# Mobo.net
KiCad netlist of a schematic drawn in Altium Designer
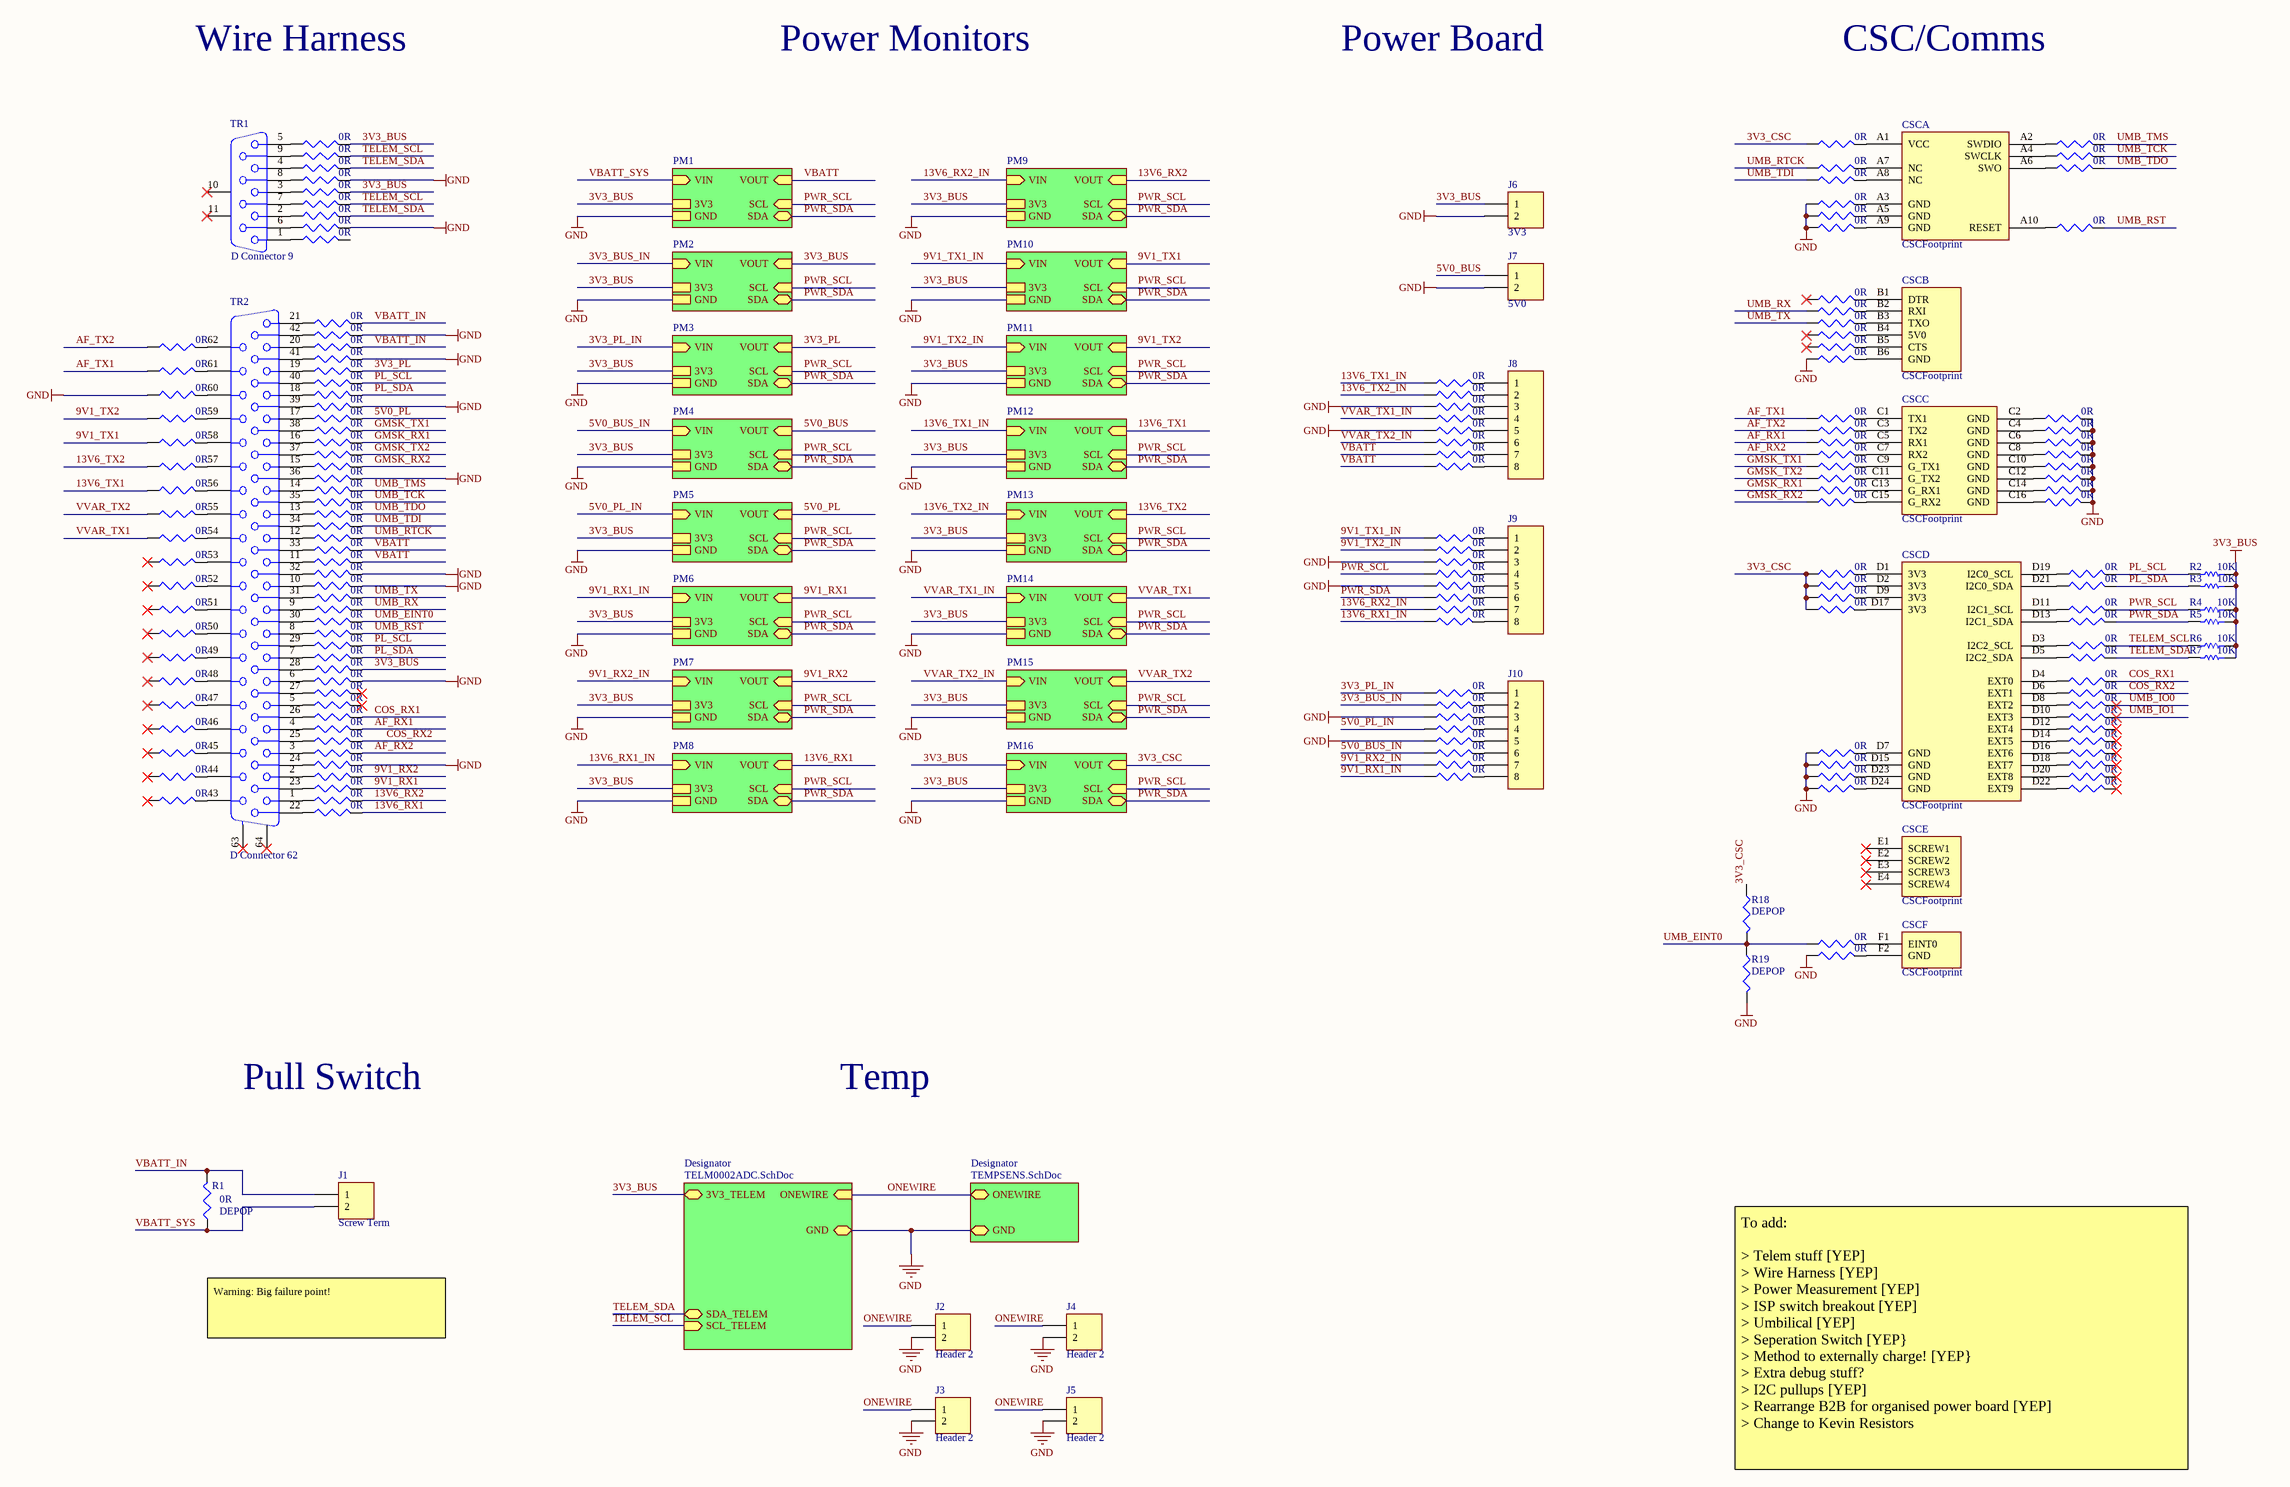
[diagram p0: Mobo.SchDoc]

(export (version "E")
  (design (tool "Eeschema 10.0.6"))
  (components
    (comp (ref "CSC")
      (value "CSCFootprint")
      (footprint "CSCFootprint")
      (libsource (lib "Tray2Mobo") (part "CSCFootprint"))
    )
    (comp (ref "J1")
      (value "Screw Term")
      (footprint "100mil ScrewTerm")
      (description "Header, 2-Pin")
      (fields (field (name "PUBLISHER") "Altium Limited"))
      (libsource (lib "Miscellaneous Connectors") (part "1WIRE"))
    )
    (comp (ref "J2")
      (value "Header 2")
      (footprint "HDR1X2")
      (description "Header, 2-Pin")
      (fields (field (name "PUBLISHER") "Altium Limited"))
      (libsource (lib "Miscellaneous Connectors") (part "1WIRE"))
    )
    (comp (ref "J3")
      (value "Header 2")
      (footprint "HDR1X2")
      (description "Header, 2-Pin")
      (fields (field (name "PUBLISHER") "Altium Limited"))
      (libsource (lib "Miscellaneous Connectors") (part "1WIRE"))
    )
    (comp (ref "J4")
      (value "Header 2")
      (footprint "HDR1X2")
      (description "Header, 2-Pin")
      (fields (field (name "PUBLISHER") "Altium Limited"))
      (libsource (lib "Miscellaneous Connectors") (part "1WIRE"))
    )
    (comp (ref "J5")
      (value "Header 2")
      (footprint "HDR1X2")
      (description "Header, 2-Pin")
      (fields (field (name "PUBLISHER") "Altium Limited"))
      (libsource (lib "Miscellaneous Connectors") (part "1WIRE"))
    )
    (comp (ref "J6")
      (value "3V3")
      (footprint "HDR1X2")
      (description "Header, 2-Pin")
      (fields (field (name "PUBLISHER") "Altium Limited"))
      (libsource (lib "Miscellaneous Connectors") (part "Header 2"))
    )
    (comp (ref "J7")
      (value "5V0")
      (footprint "HDR1X2")
      (description "Header, 2-Pin")
      (fields (field (name "PUBLISHER") "Altium Limited"))
      (libsource (lib "Miscellaneous Connectors") (part "Header 2"))
    )
    (comp (ref "J8")
      (value "J?")
      (footprint "MOLEX 444280802")
      (description "B2B RA Header")
      (libsource (lib "Tray2Mobo") (part "MOLEX 444280802"))
    )
    (comp (ref "J9")
      (value "J?")
      (footprint "MOLEX 444280802")
      (description "B2B RA Header")
      (libsource (lib "Tray2Mobo") (part "MOLEX 444280802"))
    )
    (comp (ref "J10")
      (value "J?")
      (footprint "MOLEX 444280802")
      (description "B2B RA Header")
      (libsource (lib "Tray2Mobo") (part "MOLEX 444280802"))
    )
    (comp (ref "R1")
      (value "DEPOP")
      (footprint "R0402M")
      (description "Resistor")
      (fields (field (name "ALTIUM_VALUE") "0R") (field (name "PUBLISHER") "Altium Limited"))
      (libsource (lib "Miscellaneous Devices") (part "Res3"))
    )
    (comp (ref "R2")
      (value "10K")
      (footprint "R0402M")
      (description "Resistor")
      (fields (field (name "PUBLISHER") "Altium Limited"))
      (libsource (lib "Miscellaneous Devices") (part "Res1"))
    )
    (comp (ref "R3")
      (value "10K")
      (footprint "R0402M")
      (description "Resistor")
      (fields (field (name "PUBLISHER") "Altium Limited"))
      (libsource (lib "Miscellaneous Devices") (part "Res1"))
    )
    (comp (ref "R4")
      (value "10K")
      (footprint "R0402M")
      (description "Resistor")
      (fields (field (name "PUBLISHER") "Altium Limited"))
      (libsource (lib "Miscellaneous Devices") (part "Res1"))
    )
    (comp (ref "R5")
      (value "10K")
      (footprint "R0402M")
      (description "Resistor")
      (fields (field (name "PUBLISHER") "Altium Limited"))
      (libsource (lib "Miscellaneous Devices") (part "Res1"))
    )
    (comp (ref "R6")
      (value "10K")
      (footprint "R0402M")
      (description "Resistor")
      (fields (field (name "PUBLISHER") "Altium Limited"))
      (libsource (lib "Miscellaneous Devices") (part "Res1"))
    )
    (comp (ref "R7")
      (value "10K")
      (footprint "R0402M")
      (description "Resistor")
      (fields (field (name "PUBLISHER") "Altium Limited"))
      (libsource (lib "Miscellaneous Devices") (part "Res1"))
    )
    (comp (ref "R18")
      (value "DEPOP")
      (footprint "R0402M")
      (description "Resistor")
      (fields (field (name "PUBLISHER") "Altium Limited"))
      (libsource (lib "Miscellaneous Devices") (part "Res3"))
    )
    (comp (ref "R19")
      (value "DEPOP")
      (footprint "R0402M")
      (description "Resistor")
      (fields (field (name "PUBLISHER") "Altium Limited"))
      (libsource (lib "Miscellaneous Devices") (part "Res3"))
    )
    (comp (ref "TR1")
      (value "D Connector 9")
      (footprint "HD-20 9 POS")
      (description "Receptacle Assembly, 9 Position, Right Angle")
      (fields (field (name "PUBLISHER") "Altium Limited"))
      (libsource (lib "Miscellaneous Connectors") (part "D Connector 9"))
    )
    (comp (ref "TR2")
      (value "D Connector 62")
      (footprint "HD-22 62 POS")
      (libsource (lib "Tray2Mobo") (part "Connector 62"))
    )
    (comp (ref "Z1")
      (value "0R")
      (footprint "Short")
      (description "Resistor")
      (fields (field (name "PUBLISHER") "Altium Limited"))
      (libsource (lib "Miscellaneous Devices") (part "Res3"))
    )
    (comp (ref "Z2")
      (value "0R")
      (footprint "Short")
      (description "Resistor")
      (fields (field (name "PUBLISHER") "Altium Limited"))
      (libsource (lib "Miscellaneous Devices") (part "Res3"))
    )
    (comp (ref "Z3")
      (value "0R")
      (footprint "Short")
      (description "Resistor")
      (fields (field (name "PUBLISHER") "Altium Limited"))
      (libsource (lib "Miscellaneous Devices") (part "Res3"))
    )
    (comp (ref "Z4")
      (value "0R")
      (footprint "Short")
      (description "Resistor")
      (fields (field (name "PUBLISHER") "Altium Limited"))
      (libsource (lib "Miscellaneous Devices") (part "Res3"))
    )
    (comp (ref "Z5")
      (value "0R")
      (footprint "Short")
      (description "Resistor")
      (fields (field (name "PUBLISHER") "Altium Limited"))
      (libsource (lib "Miscellaneous Devices") (part "Res3"))
    )
    (comp (ref "Z6")
      (value "0R")
      (footprint "Short")
      (description "Resistor")
      (fields (field (name "PUBLISHER") "Altium Limited"))
      (libsource (lib "Miscellaneous Devices") (part "Res3"))
    )
    (comp (ref "Z7")
      (value "0R")
      (footprint "Short")
      (description "Resistor")
      (fields (field (name "PUBLISHER") "Altium Limited"))
      (libsource (lib "Miscellaneous Devices") (part "Res3"))
    )
    (comp (ref "Z8")
      (value "0R")
      (footprint "Short")
      (description "Resistor")
      (fields (field (name "PUBLISHER") "Altium Limited"))
      (libsource (lib "Miscellaneous Devices") (part "Res3"))
    )
    (comp (ref "Z9")
      (value "0R")
      (footprint "Short")
      (description "Resistor")
      (fields (field (name "PUBLISHER") "Altium Limited"))
      (libsource (lib "Miscellaneous Devices") (part "Res3"))
    )
    (comp (ref "Z10")
      (value "0R")
      (footprint "Short")
      (description "Resistor")
      (fields (field (name "PUBLISHER") "Altium Limited"))
      (libsource (lib "Miscellaneous Devices") (part "Res3"))
    )
    (comp (ref "Z11")
      (value "0R")
      (footprint "Short")
      (description "Resistor")
      (fields (field (name "PUBLISHER") "Altium Limited"))
      (libsource (lib "Miscellaneous Devices") (part "Res3"))
    )
    (comp (ref "Z12")
      (value "0R")
      (footprint "Short")
      (description "Resistor")
      (fields (field (name "PUBLISHER") "Altium Limited"))
      (libsource (lib "Miscellaneous Devices") (part "Res3"))
    )
    (comp (ref "Z13")
      (value "0R")
      (footprint "Short")
      (description "Resistor")
      (fields (field (name "PUBLISHER") "Altium Limited"))
      (libsource (lib "Miscellaneous Devices") (part "Res3"))
    )
    (comp (ref "Z14")
      (value "0R")
      (footprint "Short")
      (description "Resistor")
      (fields (field (name "PUBLISHER") "Altium Limited"))
      (libsource (lib "Miscellaneous Devices") (part "Res3"))
    )
    (comp (ref "Z15")
      (value "0R")
      (footprint "Short")
      (description "Resistor")
      (fields (field (name "PUBLISHER") "Altium Limited"))
      (libsource (lib "Miscellaneous Devices") (part "Res3"))
    )
    (comp (ref "Z16")
      (value "0R")
      (footprint "Short")
      (description "Resistor")
      (fields (field (name "PUBLISHER") "Altium Limited"))
      (libsource (lib "Miscellaneous Devices") (part "Res3"))
    )
    (comp (ref "Z17")
      (value "0R")
      (footprint "Short")
      (description "Resistor")
      (fields (field (name "PUBLISHER") "Altium Limited"))
      (libsource (lib "Miscellaneous Devices") (part "Res3"))
    )
    (comp (ref "Z18")
      (value "0R")
      (footprint "Short")
      (description "Resistor")
      (fields (field (name "PUBLISHER") "Altium Limited"))
      (libsource (lib "Miscellaneous Devices") (part "Res3"))
    )
    (comp (ref "Z19")
      (value "0R")
      (footprint "Short")
      (description "Resistor")
      (fields (field (name "PUBLISHER") "Altium Limited"))
      (libsource (lib "Miscellaneous Devices") (part "Res3"))
    )
    (comp (ref "Z20")
      (value "0R")
      (footprint "Short")
      (description "Resistor")
      (fields (field (name "PUBLISHER") "Altium Limited"))
      (libsource (lib "Miscellaneous Devices") (part "Res3"))
    )
    (comp (ref "Z21")
      (value "0R")
      (footprint "Short")
      (description "Resistor")
      (fields (field (name "PUBLISHER") "Altium Limited"))
      (libsource (lib "Miscellaneous Devices") (part "Res3"))
    )
    (comp (ref "Z22")
      (value "0R")
      (footprint "Short")
      (description "Resistor")
      (fields (field (name "PUBLISHER") "Altium Limited"))
      (libsource (lib "Miscellaneous Devices") (part "Res3"))
    )
    (comp (ref "Z23")
      (value "0R")
      (footprint "Short")
      (description "Resistor")
      (fields (field (name "PUBLISHER") "Altium Limited"))
      (libsource (lib "Miscellaneous Devices") (part "Res3"))
    )
    (comp (ref "Z24")
      (value "0R")
      (footprint "Short")
      (description "Resistor")
      (fields (field (name "PUBLISHER") "Altium Limited"))
      (libsource (lib "Miscellaneous Devices") (part "Res3"))
    )
    (comp (ref "Z25")
      (value "0R")
      (footprint "Short")
      (description "Resistor")
      (fields (field (name "PUBLISHER") "Altium Limited"))
      (libsource (lib "Miscellaneous Devices") (part "Res3"))
    )
    (comp (ref "Z26")
      (value "0R")
      (footprint "Short")
      (description "Resistor")
      (fields (field (name "PUBLISHER") "Altium Limited"))
      (libsource (lib "Miscellaneous Devices") (part "Res3"))
    )
    (comp (ref "Z27")
      (value "0R")
      (footprint "Short")
      (description "Resistor")
      (fields (field (name "PUBLISHER") "Altium Limited"))
      (libsource (lib "Miscellaneous Devices") (part "Res3"))
    )
    (comp (ref "Z28")
      (value "0R")
      (footprint "Short")
      (description "Resistor")
      (fields (field (name "PUBLISHER") "Altium Limited"))
      (libsource (lib "Miscellaneous Devices") (part "Res3"))
    )
    (comp (ref "Z29")
      (value "0R")
      (footprint "Short")
      (description "Resistor")
      (fields (field (name "PUBLISHER") "Altium Limited"))
      (libsource (lib "Miscellaneous Devices") (part "Res3"))
    )
    (comp (ref "Z30")
      (value "0R")
      (footprint "Short")
      (description "Resistor")
      (fields (field (name "PUBLISHER") "Altium Limited"))
      (libsource (lib "Miscellaneous Devices") (part "Res3"))
    )
    (comp (ref "Z31")
      (value "0R")
      (footprint "Short")
      (description "Resistor")
      (fields (field (name "PUBLISHER") "Altium Limited"))
      (libsource (lib "Miscellaneous Devices") (part "Res3"))
    )
    (comp (ref "Z32")
      (value "0R")
      (footprint "Short")
      (description "Resistor")
      (fields (field (name "PUBLISHER") "Altium Limited"))
      (libsource (lib "Miscellaneous Devices") (part "Res3"))
    )
    (comp (ref "Z33")
      (value "0R")
      (footprint "Short")
      (description "Resistor")
      (fields (field (name "PUBLISHER") "Altium Limited"))
      (libsource (lib "Miscellaneous Devices") (part "Res3"))
    )
    (comp (ref "Z34")
      (value "0R")
      (footprint "Short")
      (description "Resistor")
      (fields (field (name "PUBLISHER") "Altium Limited"))
      (libsource (lib "Miscellaneous Devices") (part "Res3"))
    )
    (comp (ref "Z35")
      (value "0R")
      (footprint "Short")
      (description "Resistor")
      (fields (field (name "PUBLISHER") "Altium Limited"))
      (libsource (lib "Miscellaneous Devices") (part "Res3"))
    )
    (comp (ref "Z36")
      (value "0R")
      (footprint "Short")
      (description "Resistor")
      (fields (field (name "PUBLISHER") "Altium Limited"))
      (libsource (lib "Miscellaneous Devices") (part "Res3"))
    )
    (comp (ref "Z37")
      (value "0R")
      (footprint "Short")
      (description "Resistor")
      (fields (field (name "PUBLISHER") "Altium Limited"))
      (libsource (lib "Miscellaneous Devices") (part "Res3"))
    )
    (comp (ref "Z38")
      (value "0R")
      (footprint "Short")
      (description "Resistor")
      (fields (field (name "PUBLISHER") "Altium Limited"))
      (libsource (lib "Miscellaneous Devices") (part "Res3"))
    )
    (comp (ref "Z39")
      (value "0R")
      (footprint "Short")
      (description "Resistor")
      (fields (field (name "PUBLISHER") "Altium Limited"))
      (libsource (lib "Miscellaneous Devices") (part "Res3"))
    )
    (comp (ref "Z40")
      (value "0R")
      (footprint "Short")
      (description "Resistor")
      (fields (field (name "PUBLISHER") "Altium Limited"))
      (libsource (lib "Miscellaneous Devices") (part "Res3"))
    )
    (comp (ref "Z41")
      (value "0R")
      (footprint "Short")
      (description "Resistor")
      (fields (field (name "PUBLISHER") "Altium Limited"))
      (libsource (lib "Miscellaneous Devices") (part "Res3"))
    )
    (comp (ref "Z42")
      (value "0R")
      (footprint "Short")
      (description "Resistor")
      (fields (field (name "PUBLISHER") "Altium Limited"))
      (libsource (lib "Miscellaneous Devices") (part "Res3"))
    )
    (comp (ref "Z43")
      (value "0R")
      (footprint "Short")
      (description "Resistor")
      (fields (field (name "PUBLISHER") "Altium Limited"))
      (libsource (lib "Miscellaneous Devices") (part "Res3"))
    )
    (comp (ref "Z44")
      (value "0R")
      (footprint "Short")
      (description "Resistor")
      (fields (field (name "PUBLISHER") "Altium Limited"))
      (libsource (lib "Miscellaneous Devices") (part "Res3"))
    )
    (comp (ref "Z45")
      (value "0R")
      (footprint "Short")
      (description "Resistor")
      (fields (field (name "PUBLISHER") "Altium Limited"))
      (libsource (lib "Miscellaneous Devices") (part "Res3"))
    )
    (comp (ref "Z46")
      (value "0R")
      (footprint "Short")
      (description "Resistor")
      (fields (field (name "PUBLISHER") "Altium Limited"))
      (libsource (lib "Miscellaneous Devices") (part "Res3"))
    )
    (comp (ref "Z47")
      (value "0R")
      (footprint "Short")
      (description "Resistor")
      (fields (field (name "PUBLISHER") "Altium Limited"))
      (libsource (lib "Miscellaneous Devices") (part "Res3"))
    )
    (comp (ref "Z48")
      (value "0R")
      (footprint "Short")
      (description "Resistor")
      (fields (field (name "PUBLISHER") "Altium Limited"))
      (libsource (lib "Miscellaneous Devices") (part "Res3"))
    )
    (comp (ref "Z49")
      (value "0R")
      (footprint "Short")
      (description "Resistor")
      (fields (field (name "PUBLISHER") "Altium Limited"))
      (libsource (lib "Miscellaneous Devices") (part "Res3"))
    )
    (comp (ref "Z50")
      (value "0R")
      (footprint "Short")
      (description "Resistor")
      (fields (field (name "PUBLISHER") "Altium Limited"))
      (libsource (lib "Miscellaneous Devices") (part "Res3"))
    )
    (comp (ref "Z51")
      (value "0R")
      (footprint "Short")
      (description "Resistor")
      (fields (field (name "PUBLISHER") "Altium Limited"))
      (libsource (lib "Miscellaneous Devices") (part "Res3"))
    )
    (comp (ref "Z52")
      (value "0R")
      (footprint "Short")
      (description "Resistor")
      (fields (field (name "PUBLISHER") "Altium Limited"))
      (libsource (lib "Miscellaneous Devices") (part "Res3"))
    )
    (comp (ref "Z53")
      (value "0R")
      (footprint "Short")
      (description "Resistor")
      (fields (field (name "PUBLISHER") "Altium Limited"))
      (libsource (lib "Miscellaneous Devices") (part "Res3"))
    )
    (comp (ref "Z54")
      (value "0R")
      (footprint "Short")
      (description "Resistor")
      (fields (field (name "PUBLISHER") "Altium Limited"))
      (libsource (lib "Miscellaneous Devices") (part "Res3"))
    )
    (comp (ref "Z55")
      (value "0R")
      (footprint "Short")
      (description "Resistor")
      (fields (field (name "PUBLISHER") "Altium Limited"))
      (libsource (lib "Miscellaneous Devices") (part "Res3"))
    )
    (comp (ref "Z56")
      (value "0R")
      (footprint "Short")
      (description "Resistor")
      (fields (field (name "PUBLISHER") "Altium Limited"))
      (libsource (lib "Miscellaneous Devices") (part "Res3"))
    )
    (comp (ref "Z57")
      (value "0R")
      (footprint "Short")
      (description "Resistor")
      (fields (field (name "PUBLISHER") "Altium Limited"))
      (libsource (lib "Miscellaneous Devices") (part "Res3"))
    )
    (comp (ref "Z58")
      (value "0R")
      (footprint "Short")
      (description "Resistor")
      (fields (field (name "PUBLISHER") "Altium Limited"))
      (libsource (lib "Miscellaneous Devices") (part "Res3"))
    )
    (comp (ref "Z59")
      (value "0R")
      (footprint "Short")
      (description "Resistor")
      (fields (field (name "PUBLISHER") "Altium Limited"))
      (libsource (lib "Miscellaneous Devices") (part "Res3"))
    )
    (comp (ref "Z60")
      (value "0R")
      (footprint "Short")
      (description "Resistor")
      (fields (field (name "PUBLISHER") "Altium Limited"))
      (libsource (lib "Miscellaneous Devices") (part "Res3"))
    )
    (comp (ref "Z61")
      (value "0R")
      (footprint "Short")
      (description "Resistor")
      (fields (field (name "PUBLISHER") "Altium Limited"))
      (libsource (lib "Miscellaneous Devices") (part "Res3"))
    )
    (comp (ref "Z62")
      (value "0R")
      (footprint "Short")
      (description "Resistor")
      (fields (field (name "PUBLISHER") "Altium Limited"))
      (libsource (lib "Miscellaneous Devices") (part "Res3"))
    )
    (comp (ref "Z63")
      (value "0R")
      (footprint "Short")
      (description "Resistor")
      (fields (field (name "PUBLISHER") "Altium Limited"))
      (libsource (lib "Miscellaneous Devices") (part "Res3"))
    )
    (comp (ref "Z64")
      (value "0R")
      (footprint "Short")
      (description "Resistor")
      (fields (field (name "PUBLISHER") "Altium Limited"))
      (libsource (lib "Miscellaneous Devices") (part "Res3"))
    )
    (comp (ref "Z65")
      (value "0R")
      (footprint "Short")
      (description "Resistor")
      (fields (field (name "PUBLISHER") "Altium Limited"))
      (libsource (lib "Miscellaneous Devices") (part "Res3"))
    )
    (comp (ref "Z66")
      (value "0R")
      (footprint "Short")
      (description "Resistor")
      (fields (field (name "PUBLISHER") "Altium Limited"))
      (libsource (lib "Miscellaneous Devices") (part "Res3"))
    )
    (comp (ref "Z67")
      (value "0R")
      (footprint "Short")
      (description "Resistor")
      (fields (field (name "PUBLISHER") "Altium Limited"))
      (libsource (lib "Miscellaneous Devices") (part "Res3"))
    )
    (comp (ref "Z68")
      (value "0R")
      (footprint "Short")
      (description "Resistor")
      (fields (field (name "PUBLISHER") "Altium Limited"))
      (libsource (lib "Miscellaneous Devices") (part "Res3"))
    )
    (comp (ref "Z69")
      (value "0R")
      (footprint "Short")
      (description "Resistor")
      (fields (field (name "PUBLISHER") "Altium Limited"))
      (libsource (lib "Miscellaneous Devices") (part "Res3"))
    )
    (comp (ref "Z70")
      (value "0R")
      (footprint "Short")
      (description "Resistor")
      (fields (field (name "PUBLISHER") "Altium Limited"))
      (libsource (lib "Miscellaneous Devices") (part "Res3"))
    )
    (comp (ref "Z71")
      (value "0R")
      (footprint "Short")
      (description "Resistor")
      (fields (field (name "PUBLISHER") "Altium Limited"))
      (libsource (lib "Miscellaneous Devices") (part "Res3"))
    )
    (comp (ref "Z72")
      (value "0R")
      (footprint "Short")
      (description "Resistor")
      (fields (field (name "PUBLISHER") "Altium Limited"))
      (libsource (lib "Miscellaneous Devices") (part "Res3"))
    )
    (comp (ref "Z73")
      (value "0R")
      (footprint "Short")
      (description "Resistor")
      (fields (field (name "PUBLISHER") "Altium Limited"))
      (libsource (lib "Miscellaneous Devices") (part "Res3"))
    )
    (comp (ref "Z74")
      (value "0R")
      (footprint "Short")
      (description "Resistor")
      (fields (field (name "PUBLISHER") "Altium Limited"))
      (libsource (lib "Miscellaneous Devices") (part "Res3"))
    )
    (comp (ref "Z75")
      (value "0R")
      (footprint "Short")
      (description "Resistor")
      (fields (field (name "PUBLISHER") "Altium Limited"))
      (libsource (lib "Miscellaneous Devices") (part "Res3"))
    )
    (comp (ref "Z76")
      (value "0R")
      (footprint "Short")
      (description "Resistor")
      (fields (field (name "PUBLISHER") "Altium Limited"))
      (libsource (lib "Miscellaneous Devices") (part "Res3"))
    )
    (comp (ref "Z77")
      (value "0R")
      (footprint "Short")
      (description "Resistor")
      (fields (field (name "PUBLISHER") "Altium Limited"))
      (libsource (lib "Miscellaneous Devices") (part "Res3"))
    )
    (comp (ref "Z78")
      (value "0R")
      (footprint "Short")
      (description "Resistor")
      (fields (field (name "PUBLISHER") "Altium Limited"))
      (libsource (lib "Miscellaneous Devices") (part "Res3"))
    )
    (comp (ref "Z79")
      (value "0R")
      (footprint "Short")
      (description "Resistor")
      (fields (field (name "PUBLISHER") "Altium Limited"))
      (libsource (lib "Miscellaneous Devices") (part "Res3"))
    )
    (comp (ref "Z80")
      (value "0R")
      (footprint "Short")
      (description "Resistor")
      (fields (field (name "PUBLISHER") "Altium Limited"))
      (libsource (lib "Miscellaneous Devices") (part "Res3"))
    )
    (comp (ref "Z81")
      (value "0R")
      (footprint "Short")
      (description "Resistor")
      (fields (field (name "PUBLISHER") "Altium Limited"))
      (libsource (lib "Miscellaneous Devices") (part "Res3"))
    )
    (comp (ref "Z82")
      (value "0R")
      (footprint "Short")
      (description "Resistor")
      (fields (field (name "PUBLISHER") "Altium Limited"))
      (libsource (lib "Miscellaneous Devices") (part "Res3"))
    )
    (comp (ref "Z83")
      (value "0R")
      (footprint "Short")
      (description "Resistor")
      (fields (field (name "PUBLISHER") "Altium Limited"))
      (libsource (lib "Miscellaneous Devices") (part "Res3"))
    )
    (comp (ref "Z84")
      (value "0R")
      (footprint "Short")
      (description "Resistor")
      (fields (field (name "PUBLISHER") "Altium Limited"))
      (libsource (lib "Miscellaneous Devices") (part "Res3"))
    )
    (comp (ref "Z85")
      (value "0R")
      (footprint "Short")
      (description "Resistor")
      (fields (field (name "PUBLISHER") "Altium Limited"))
      (libsource (lib "Miscellaneous Devices") (part "Res3"))
    )
    (comp (ref "Z86")
      (value "0R")
      (footprint "Short")
      (description "Resistor")
      (fields (field (name "PUBLISHER") "Altium Limited"))
      (libsource (lib "Miscellaneous Devices") (part "Res3"))
    )
    (comp (ref "Z87")
      (value "0R")
      (footprint "Short")
      (description "Resistor")
      (fields (field (name "PUBLISHER") "Altium Limited"))
      (libsource (lib "Miscellaneous Devices") (part "Res3"))
    )
    (comp (ref "Z88")
      (value "0R")
      (footprint "Short")
      (description "Resistor")
      (fields (field (name "PUBLISHER") "Altium Limited"))
      (libsource (lib "Miscellaneous Devices") (part "Res3"))
    )
    (comp (ref "Z89")
      (value "0R")
      (footprint "Short")
      (description "Resistor")
      (fields (field (name "PUBLISHER") "Altium Limited"))
      (libsource (lib "Miscellaneous Devices") (part "Res3"))
    )
    (comp (ref "Z90")
      (value "0R")
      (footprint "Short")
      (description "Resistor")
      (fields (field (name "PUBLISHER") "Altium Limited"))
      (libsource (lib "Miscellaneous Devices") (part "Res3"))
    )
    (comp (ref "Z91")
      (value "0R")
      (footprint "Short")
      (description "Resistor")
      (fields (field (name "PUBLISHER") "Altium Limited"))
      (libsource (lib "Miscellaneous Devices") (part "Res3"))
    )
    (comp (ref "Z92")
      (value "0R")
      (footprint "Short")
      (description "Resistor")
      (fields (field (name "PUBLISHER") "Altium Limited"))
      (libsource (lib "Miscellaneous Devices") (part "Res3"))
    )
    (comp (ref "Z93")
      (value "0R")
      (footprint "Short")
      (description "Resistor")
      (fields (field (name "PUBLISHER") "Altium Limited"))
      (libsource (lib "Miscellaneous Devices") (part "Res3"))
    )
    (comp (ref "Z94")
      (value "0R")
      (footprint "Short")
      (description "Resistor")
      (fields (field (name "PUBLISHER") "Altium Limited"))
      (libsource (lib "Miscellaneous Devices") (part "Res3"))
    )
    (comp (ref "Z95")
      (value "0R")
      (footprint "Short")
      (description "Resistor")
      (fields (field (name "PUBLISHER") "Altium Limited"))
      (libsource (lib "Miscellaneous Devices") (part "Res3"))
    )
    (comp (ref "Z96")
      (value "0R")
      (footprint "Short")
      (description "Resistor")
      (fields (field (name "PUBLISHER") "Altium Limited"))
      (libsource (lib "Miscellaneous Devices") (part "Res3"))
    )
    (comp (ref "Z97")
      (value "0R")
      (footprint "Short")
      (description "Resistor")
      (fields (field (name "PUBLISHER") "Altium Limited"))
      (libsource (lib "Miscellaneous Devices") (part "Res3"))
    )
    (comp (ref "Z98")
      (value "0R")
      (footprint "Short")
      (description "Resistor")
      (fields (field (name "PUBLISHER") "Altium Limited"))
      (libsource (lib "Miscellaneous Devices") (part "Res3"))
    )
    (comp (ref "Z99")
      (value "0R")
      (footprint "Short")
      (description "Resistor")
      (fields (field (name "PUBLISHER") "Altium Limited"))
      (libsource (lib "Miscellaneous Devices") (part "Res3"))
    )
    (comp (ref "Z100")
      (value "0R")
      (footprint "Short")
      (description "Resistor")
      (fields (field (name "PUBLISHER") "Altium Limited"))
      (libsource (lib "Miscellaneous Devices") (part "Res3"))
    )
    (comp (ref "Z101")
      (value "0R")
      (footprint "Short")
      (description "Resistor")
      (fields (field (name "PUBLISHER") "Altium Limited"))
      (libsource (lib "Miscellaneous Devices") (part "Res3"))
    )
    (comp (ref "Z102")
      (value "0R")
      (footprint "Short")
      (description "Resistor")
      (fields (field (name "PUBLISHER") "Altium Limited"))
      (libsource (lib "Miscellaneous Devices") (part "Res3"))
    )
    (comp (ref "Z103")
      (value "0R")
      (footprint "Short")
      (description "Resistor")
      (fields (field (name "PUBLISHER") "Altium Limited"))
      (libsource (lib "Miscellaneous Devices") (part "Res3"))
    )
    (comp (ref "Z104")
      (value "0R")
      (footprint "Short")
      (description "Resistor")
      (fields (field (name "PUBLISHER") "Altium Limited"))
      (libsource (lib "Miscellaneous Devices") (part "Res3"))
    )
    (comp (ref "Z105")
      (value "0R")
      (footprint "Short")
      (description "Resistor")
      (fields (field (name "PUBLISHER") "Altium Limited"))
      (libsource (lib "Miscellaneous Devices") (part "Res3"))
    )
    (comp (ref "Z106")
      (value "0R")
      (footprint "Short")
      (description "Resistor")
      (fields (field (name "PUBLISHER") "Altium Limited"))
      (libsource (lib "Miscellaneous Devices") (part "Res3"))
    )
    (comp (ref "Z107")
      (value "0R")
      (footprint "Short")
      (description "Resistor")
      (fields (field (name "PUBLISHER") "Altium Limited"))
      (libsource (lib "Miscellaneous Devices") (part "Res3"))
    )
    (comp (ref "Z108")
      (value "0R")
      (footprint "Short")
      (description "Resistor")
      (fields (field (name "PUBLISHER") "Altium Limited"))
      (libsource (lib "Miscellaneous Devices") (part "Res3"))
    )
    (comp (ref "Z109")
      (value "0R")
      (footprint "Short")
      (description "Resistor")
      (fields (field (name "PUBLISHER") "Altium Limited"))
      (libsource (lib "Miscellaneous Devices") (part "Res3"))
    )
    (comp (ref "Z110")
      (value "0R")
      (footprint "Short")
      (description "Resistor")
      (fields (field (name "PUBLISHER") "Altium Limited"))
      (libsource (lib "Miscellaneous Devices") (part "Res3"))
    )
    (comp (ref "Z111")
      (value "0R")
      (footprint "Short")
      (description "Resistor")
      (fields (field (name "PUBLISHER") "Altium Limited"))
      (libsource (lib "Miscellaneous Devices") (part "Res3"))
    )
    (comp (ref "Z112")
      (value "0R")
      (footprint "Short")
      (description "Resistor")
      (fields (field (name "PUBLISHER") "Altium Limited"))
      (libsource (lib "Miscellaneous Devices") (part "Res3"))
    )
    (comp (ref "Z113")
      (value "0R")
      (footprint "Short")
      (description "Resistor")
      (fields (field (name "PUBLISHER") "Altium Limited"))
      (libsource (lib "Miscellaneous Devices") (part "Res3"))
    )
    (comp (ref "Z114")
      (value "0R")
      (footprint "Short")
      (description "Resistor")
      (fields (field (name "PUBLISHER") "Altium Limited"))
      (libsource (lib "Miscellaneous Devices") (part "Res3"))
    )
    (comp (ref "Z115")
      (value "0R")
      (footprint "Short")
      (description "Resistor")
      (fields (field (name "PUBLISHER") "Altium Limited"))
      (libsource (lib "Miscellaneous Devices") (part "Res3"))
    )
    (comp (ref "Z116")
      (value "0R")
      (footprint "Short")
      (description "Resistor")
      (fields (field (name "PUBLISHER") "Altium Limited"))
      (libsource (lib "Miscellaneous Devices") (part "Res3"))
    )
    (comp (ref "Z117")
      (value "0R")
      (footprint "Short")
      (description "Resistor")
      (fields (field (name "PUBLISHER") "Altium Limited"))
      (libsource (lib "Miscellaneous Devices") (part "Res3"))
    )
    (comp (ref "Z118")
      (value "0R")
      (footprint "Short")
      (description "Resistor")
      (fields (field (name "PUBLISHER") "Altium Limited"))
      (libsource (lib "Miscellaneous Devices") (part "Res3"))
    )
    (comp (ref "Z119")
      (value "0R")
      (footprint "Short")
      (description "Resistor")
      (fields (field (name "PUBLISHER") "Altium Limited"))
      (libsource (lib "Miscellaneous Devices") (part "Res3"))
    )
    (comp (ref "Z120")
      (value "0R")
      (footprint "Short")
      (description "Resistor")
      (fields (field (name "PUBLISHER") "Altium Limited"))
      (libsource (lib "Miscellaneous Devices") (part "Res3"))
    )
    (comp (ref "Z121")
      (value "0R")
      (footprint "Short")
      (description "Resistor")
      (fields (field (name "PUBLISHER") "Altium Limited"))
      (libsource (lib "Miscellaneous Devices") (part "Res3"))
    )
    (comp (ref "Z122")
      (value "0R")
      (footprint "Short")
      (description "Resistor")
      (fields (field (name "PUBLISHER") "Altium Limited"))
      (libsource (lib "Miscellaneous Devices") (part "Res3"))
    )
    (comp (ref "Z123")
      (value "0R")
      (footprint "Short")
      (description "Resistor")
      (fields (field (name "PUBLISHER") "Altium Limited"))
      (libsource (lib "Miscellaneous Devices") (part "Res3"))
    )
    (comp (ref "Z124")
      (value "0R")
      (footprint "Short")
      (description "Resistor")
      (fields (field (name "PUBLISHER") "Altium Limited"))
      (libsource (lib "Miscellaneous Devices") (part "Res3"))
    )
    (comp (ref "Z125")
      (value "0R")
      (footprint "Short")
      (description "Resistor")
      (fields (field (name "PUBLISHER") "Altium Limited"))
      (libsource (lib "Miscellaneous Devices") (part "Res3"))
    )
    (comp (ref "Z126")
      (value "0R")
      (footprint "Short")
      (description "Resistor")
      (fields (field (name "PUBLISHER") "Altium Limited"))
      (libsource (lib "Miscellaneous Devices") (part "Res3"))
    )
    (comp (ref "Z127")
      (value "0R")
      (footprint "Short")
      (description "Resistor")
      (fields (field (name "PUBLISHER") "Altium Limited"))
      (libsource (lib "Miscellaneous Devices") (part "Res3"))
    )
    (comp (ref "Z128")
      (value "0R")
      (footprint "Short")
      (description "Resistor")
      (fields (field (name "PUBLISHER") "Altium Limited"))
      (libsource (lib "Miscellaneous Devices") (part "Res3"))
    )
    (comp (ref "Z129")
      (value "0R")
      (footprint "Short")
      (description "Resistor")
      (fields (field (name "PUBLISHER") "Altium Limited"))
      (libsource (lib "Miscellaneous Devices") (part "Res3"))
    )
    (comp (ref "Z130")
      (value "0R")
      (footprint "Short")
      (description "Resistor")
      (fields (field (name "PUBLISHER") "Altium Limited"))
      (libsource (lib "Miscellaneous Devices") (part "Res3"))
    )
    (comp (ref "Z131")
      (value "0R")
      (footprint "Short")
      (description "Resistor")
      (fields (field (name "PUBLISHER") "Altium Limited"))
      (libsource (lib "Miscellaneous Devices") (part "Res3"))
    )
    (comp (ref "Z132")
      (value "0R")
      (footprint "Short")
      (description "Resistor")
      (fields (field (name "PUBLISHER") "Altium Limited"))
      (libsource (lib "Miscellaneous Devices") (part "Res3"))
    )
    (comp (ref "Z133")
      (value "0R")
      (footprint "Short")
      (description "Resistor")
      (fields (field (name "PUBLISHER") "Altium Limited"))
      (libsource (lib "Miscellaneous Devices") (part "Res3"))
    )
    (comp (ref "Z134")
      (value "0R")
      (footprint "Short")
      (description "Resistor")
      (fields (field (name "PUBLISHER") "Altium Limited"))
      (libsource (lib "Miscellaneous Devices") (part "Res3"))
    )
    (comp (ref "Z135")
      (value "0R")
      (footprint "Short")
      (description "Resistor")
      (fields (field (name "PUBLISHER") "Altium Limited"))
      (libsource (lib "Miscellaneous Devices") (part "Res3"))
    )
    (comp (ref "Z136")
      (value "0R")
      (footprint "Short")
      (description "Resistor")
      (fields (field (name "PUBLISHER") "Altium Limited"))
      (libsource (lib "Miscellaneous Devices") (part "Res3"))
    )
    (comp (ref "Z137")
      (value "0R")
      (footprint "Short")
      (description "Resistor")
      (fields (field (name "PUBLISHER") "Altium Limited"))
      (libsource (lib "Miscellaneous Devices") (part "Res3"))
    )
    (comp (ref "Z138")
      (value "0R")
      (footprint "Short")
      (description "Resistor")
      (fields (field (name "PUBLISHER") "Altium Limited"))
      (libsource (lib "Miscellaneous Devices") (part "Res3"))
    )
    (comp (ref "Z139")
      (value "0R")
      (footprint "Short")
      (description "Resistor")
      (fields (field (name "PUBLISHER") "Altium Limited"))
      (libsource (lib "Miscellaneous Devices") (part "Res3"))
    )
    (comp (ref "Z140")
      (value "0R")
      (footprint "Short")
      (description "Resistor")
      (fields (field (name "PUBLISHER") "Altium Limited"))
      (libsource (lib "Miscellaneous Devices") (part "Res3"))
    )
    (comp (ref "Z141")
      (value "0R")
      (footprint "Short")
      (description "Resistor")
      (fields (field (name "PUBLISHER") "Altium Limited"))
      (libsource (lib "Miscellaneous Devices") (part "Res3"))
    )
    (comp (ref "Z142")
      (value "0R")
      (footprint "Short")
      (description "Resistor")
      (fields (field (name "PUBLISHER") "Altium Limited"))
      (libsource (lib "Miscellaneous Devices") (part "Res3"))
    )
    (comp (ref "Z143")
      (value "0R")
      (footprint "Short")
      (description "Resistor")
      (fields (field (name "PUBLISHER") "Altium Limited"))
      (libsource (lib "Miscellaneous Devices") (part "Res3"))
    )
    (comp (ref "Z144")
      (value "0R")
      (footprint "Short")
      (description "Resistor")
      (fields (field (name "PUBLISHER") "Altium Limited"))
      (libsource (lib "Miscellaneous Devices") (part "Res3"))
    )
    (comp (ref "Z145")
      (value "0R")
      (footprint "Short")
      (description "Resistor")
      (fields (field (name "PUBLISHER") "Altium Limited"))
      (libsource (lib "Miscellaneous Devices") (part "Res3"))
    )
    (comp (ref "Z146")
      (value "0R")
      (footprint "Short")
      (description "Resistor")
      (fields (field (name "PUBLISHER") "Altium Limited"))
      (libsource (lib "Miscellaneous Devices") (part "Res3"))
    )
    (comp (ref "Z147")
      (value "0R")
      (footprint "Short")
      (description "Resistor")
      (fields (field (name "PUBLISHER") "Altium Limited"))
      (libsource (lib "Miscellaneous Devices") (part "Res3"))
    )
    (comp (ref "Z148")
      (value "0R")
      (footprint "Short")
      (description "Resistor")
      (fields (field (name "PUBLISHER") "Altium Limited"))
      (libsource (lib "Miscellaneous Devices") (part "Res3"))
    )
    (comp (ref "Z149")
      (value "0R")
      (footprint "Short")
      (description "Resistor")
      (fields (field (name "PUBLISHER") "Altium Limited"))
      (libsource (lib "Miscellaneous Devices") (part "Res3"))
    )
    (comp (ref "Z150")
      (value "0R")
      (footprint "Short")
      (description "Resistor")
      (fields (field (name "PUBLISHER") "Altium Limited"))
      (libsource (lib "Miscellaneous Devices") (part "Res3"))
    )
    (comp (ref "Z151")
      (value "0R")
      (footprint "Short")
      (description "Resistor")
      (fields (field (name "PUBLISHER") "Altium Limited"))
      (libsource (lib "Miscellaneous Devices") (part "Res3"))
    )
    (comp (ref "Z152")
      (value "0R")
      (footprint "Short")
      (description "Resistor")
      (fields (field (name "PUBLISHER") "Altium Limited"))
      (libsource (lib "Miscellaneous Devices") (part "Res3"))
    )
    (comp (ref "Z153")
      (value "0R")
      (footprint "Short")
      (description "Resistor")
      (fields (field (name "PUBLISHER") "Altium Limited"))
      (libsource (lib "Miscellaneous Devices") (part "Res3"))
    )
  )
  (nets
    (net (code "1") (name "/3V3_BUS_IN") (class "Default")
      (node (ref "Z89") (pin "1") (pinfunction "1_1") (pintype "passive"))
    )
    (net (code "2") (name "/3V3_CSC") (class "Default")
      (node (ref "R18") (pin "1") (pinfunction "1_1") (pintype "passive"))
      (node (ref "Z116") (pin "1") (pinfunction "1_1") (pintype "passive"))
      (node (ref "Z117") (pin "1") (pinfunction "1_1") (pintype "passive"))
      (node (ref "Z118") (pin "1") (pinfunction "1_1") (pintype "passive"))
      (node (ref "Z119") (pin "1") (pinfunction "1_1") (pintype "passive"))
      (node (ref "Z96") (pin "1") (pinfunction "1_1") (pintype "passive"))
    )
    (net (code "3") (name "/3V3_PL") (class "Default")
      (node (ref "Z34") (pin "2") (pinfunction "2_2") (pintype "passive"))
    )
    (net (code "4") (name "/3V3_PL_IN") (class "Default")
      (node (ref "Z88") (pin "1") (pinfunction "1_1") (pintype "passive"))
    )
    (net (code "5") (name "/5V0_BUS") (class "Default")
      (node (ref "J7") (pin "1") (pinfunction "1_1") (pintype "passive"))
    )
    (net (code "6") (name "/5V0_BUS_IN") (class "Default")
      (node (ref "Z93") (pin "1") (pinfunction "1_1") (pintype "passive"))
    )
    (net (code "7") (name "/5V0_PL") (class "Default")
      (node (ref "Z38") (pin "2") (pinfunction "2_2") (pintype "passive"))
    )
    (net (code "8") (name "/5V0_PL_IN") (class "Default")
      (node (ref "Z91") (pin "1") (pinfunction "1_1") (pintype "passive"))
    )
    (net (code "9") (name "/9V1_RX1") (class "Default")
      (node (ref "Z69") (pin "2") (pinfunction "2_2") (pintype "passive"))
    )
    (net (code "10") (name "/9V1_RX1_IN") (class "Default")
      (node (ref "Z95") (pin "1") (pinfunction "1_1") (pintype "passive"))
    )
    (net (code "11") (name "/9V1_RX2") (class "Default")
      (node (ref "Z68") (pin "2") (pinfunction "2_2") (pintype "passive"))
    )
    (net (code "12") (name "/9V1_RX2_IN") (class "Default")
      (node (ref "Z94") (pin "1") (pinfunction "1_1") (pintype "passive"))
    )
    (net (code "13") (name "/9V1_TX1") (class "Default")
      (node (ref "Z5") (pin "1") (pinfunction "1_1") (pintype "passive"))
    )
    (net (code "14") (name "/9V1_TX1_IN") (class "Default")
      (node (ref "Z80") (pin "1") (pinfunction "1_1") (pintype "passive"))
    )
    (net (code "15") (name "/9V1_TX2") (class "Default")
      (node (ref "Z4") (pin "1") (pinfunction "1_1") (pintype "passive"))
    )
    (net (code "16") (name "/9V1_TX2_IN") (class "Default")
      (node (ref "Z81") (pin "1") (pinfunction "1_1") (pintype "passive"))
    )
    (net (code "17") (name "/13V6_RX1") (class "Default")
      (node (ref "Z71") (pin "2") (pinfunction "2_2") (pintype "passive"))
    )
    (net (code "18") (name "/13V6_RX1_IN") (class "Default")
      (node (ref "Z87") (pin "1") (pinfunction "1_1") (pintype "passive"))
    )
    (net (code "19") (name "/13V6_RX2") (class "Default")
      (node (ref "Z70") (pin "2") (pinfunction "2_2") (pintype "passive"))
    )
    (net (code "20") (name "/13V6_RX2_IN") (class "Default")
      (node (ref "Z86") (pin "1") (pinfunction "1_1") (pintype "passive"))
    )
    (net (code "21") (name "/13V6_TX1") (class "Default")
      (node (ref "Z7") (pin "1") (pinfunction "1_1") (pintype "passive"))
    )
    (net (code "22") (name "/13V6_TX1_IN") (class "Default")
      (node (ref "Z72") (pin "1") (pinfunction "1_1") (pintype "passive"))
    )
    (net (code "23") (name "/13V6_TX2") (class "Default")
      (node (ref "Z6") (pin "1") (pinfunction "1_1") (pintype "passive"))
    )
    (net (code "24") (name "/13V6_TX2_IN") (class "Default")
      (node (ref "Z73") (pin "1") (pinfunction "1_1") (pintype "passive"))
    )
    (net (code "25") (name "/AF_RX1") (class "Default")
      (node (ref "Z110") (pin "1") (pinfunction "1_1") (pintype "passive"))
      (node (ref "Z64") (pin "2") (pinfunction "2_2") (pintype "passive"))
    )
    (net (code "26") (name "/AF_RX2") (class "Default")
      (node (ref "Z111") (pin "1") (pinfunction "1_1") (pintype "passive"))
      (node (ref "Z66") (pin "2") (pinfunction "2_2") (pintype "passive"))
    )
    (net (code "27") (name "/AF_TX1") (class "Default")
      (node (ref "Z108") (pin "1") (pinfunction "1_1") (pintype "passive"))
      (node (ref "Z2") (pin "1") (pinfunction "1_1") (pintype "passive"))
    )
    (net (code "28") (name "/AF_TX2") (class "Default")
      (node (ref "Z1") (pin "1") (pinfunction "1_1") (pintype "passive"))
      (node (ref "Z109") (pin "1") (pinfunction "1_1") (pintype "passive"))
    )
    (net (code "29") (name "/COS_RX1") (class "Default")
      (node (ref "Z144") (pin "2") (pinfunction "2_2") (pintype "passive"))
      (node (ref "Z63") (pin "2") (pinfunction "2_2") (pintype "passive"))
    )
    (net (code "30") (name "/COS_RX2") (class "Default")
      (node (ref "Z145") (pin "2") (pinfunction "2_2") (pintype "passive"))
      (node (ref "Z65") (pin "2") (pinfunction "2_2") (pintype "passive"))
    )
    (net (code "31") (name "/GMSK_RX1") (class "Default")
      (node (ref "Z114") (pin "1") (pinfunction "1_1") (pintype "passive"))
      (node (ref "Z40") (pin "2") (pinfunction "2_2") (pintype "passive"))
    )
    (net (code "32") (name "/GMSK_RX2") (class "Default")
      (node (ref "Z115") (pin "1") (pinfunction "1_1") (pintype "passive"))
      (node (ref "Z42") (pin "2") (pinfunction "2_2") (pintype "passive"))
    )
    (net (code "33") (name "/GMSK_TX1") (class "Default")
      (node (ref "Z112") (pin "1") (pinfunction "1_1") (pintype "passive"))
      (node (ref "Z39") (pin "2") (pinfunction "2_2") (pintype "passive"))
    )
    (net (code "34") (name "/GMSK_TX2") (class "Default")
      (node (ref "Z113") (pin "1") (pinfunction "1_1") (pintype "passive"))
      (node (ref "Z41") (pin "2") (pinfunction "2_2") (pintype "passive"))
    )
    (net (code "35") (name "/ONEWIRE") (class "Default")
      (node (ref "J2") (pin "1") (pinfunction "1_1") (pintype "passive"))
      (node (ref "J3") (pin "1") (pinfunction "1_1") (pintype "passive"))
      (node (ref "J4") (pin "1") (pinfunction "1_1") (pintype "passive"))
      (node (ref "J5") (pin "1") (pinfunction "1_1") (pintype "passive"))
    )
    (net (code "36") (name "/PL_SCL") (class "Default")
      (node (ref "R2") (pin "2") (pinfunction "2_2") (pintype "passive"))
      (node (ref "Z138") (pin "2") (pinfunction "2_2") (pintype "passive"))
      (node (ref "Z35") (pin "2") (pinfunction "2_2") (pintype "passive"))
      (node (ref "Z57") (pin "2") (pinfunction "2_2") (pintype "passive"))
    )
    (net (code "37") (name "/PL_SDA") (class "Default")
      (node (ref "R3") (pin "2") (pinfunction "2_2") (pintype "passive"))
      (node (ref "Z139") (pin "2") (pinfunction "2_2") (pintype "passive"))
      (node (ref "Z36") (pin "2") (pinfunction "2_2") (pintype "passive"))
      (node (ref "Z58") (pin "2") (pinfunction "2_2") (pintype "passive"))
    )
    (net (code "38") (name "/PWR_SCL") (class "Default")
      (node (ref "R4") (pin "2") (pinfunction "2_2") (pintype "passive"))
      (node (ref "Z140") (pin "2") (pinfunction "2_2") (pintype "passive"))
      (node (ref "Z83") (pin "1") (pinfunction "1_1") (pintype "passive"))
    )
    (net (code "39") (name "/PWR_SDA") (class "Default")
      (node (ref "R5") (pin "2") (pinfunction "2_2") (pintype "passive"))
      (node (ref "Z141") (pin "2") (pinfunction "2_2") (pintype "passive"))
      (node (ref "Z85") (pin "1") (pinfunction "1_1") (pintype "passive"))
    )
    (net (code "40") (name "/TELEM_SCL") (class "Default")
      (node (ref "R6") (pin "2") (pinfunction "2_2") (pintype "passive"))
      (node (ref "Z142") (pin "2") (pinfunction "2_2") (pintype "passive"))
      (node (ref "Z22") (pin "2") (pinfunction "2_2") (pintype "passive"))
      (node (ref "Z26") (pin "2") (pinfunction "2_2") (pintype "passive"))
    )
    (net (code "41") (name "/TELEM_SDA") (class "Default")
      (node (ref "R7") (pin "2") (pinfunction "2_2") (pintype "passive"))
      (node (ref "Z143") (pin "2") (pinfunction "2_2") (pintype "passive"))
      (node (ref "Z23") (pin "2") (pinfunction "2_2") (pintype "passive"))
      (node (ref "Z27") (pin "2") (pinfunction "2_2") (pintype "passive"))
    )
    (net (code "42") (name "/UMB_EINT0") (class "Default")
      (node (ref "R18") (pin "2") (pinfunction "2_2") (pintype "passive"))
      (node (ref "R19") (pin "1") (pinfunction "1_1") (pintype "passive"))
      (node (ref "Z124") (pin "1") (pinfunction "1_1") (pintype "passive"))
      (node (ref "Z55") (pin "2") (pinfunction "2_2") (pintype "passive"))
    )
    (net (code "43") (name "/UMB_IO0") (class "Default")
      (node (ref "Z146") (pin "2") (pinfunction "2_2") (pintype "passive+no_connect"))
    )
    (net (code "44") (name "/UMB_IO1") (class "Default")
      (node (ref "Z147") (pin "2") (pinfunction "2_2") (pintype "passive+no_connect"))
    )
    (net (code "45") (name "/UMB_RST") (class "Default")
      (node (ref "Z137") (pin "2") (pinfunction "2_2") (pintype "passive"))
      (node (ref "Z56") (pin "2") (pinfunction "2_2") (pintype "passive"))
    )
    (net (code "46") (name "/UMB_RTCK") (class "Default")
      (node (ref "Z48") (pin "2") (pinfunction "2_2") (pintype "passive"))
      (node (ref "Z97") (pin "1") (pinfunction "1_1") (pintype "passive"))
    )
    (net (code "47") (name "/UMB_RX") (class "Default")
      (node (ref "Z103") (pin "1") (pinfunction "1_1") (pintype "passive"))
      (node (ref "Z54") (pin "2") (pinfunction "2_2") (pintype "passive"))
    )
    (net (code "48") (name "/UMB_TCK") (class "Default")
      (node (ref "Z135") (pin "2") (pinfunction "2_2") (pintype "passive"))
      (node (ref "Z45") (pin "2") (pinfunction "2_2") (pintype "passive"))
    )
    (net (code "49") (name "/UMB_TDI") (class "Default")
      (node (ref "Z47") (pin "2") (pinfunction "2_2") (pintype "passive"))
      (node (ref "Z98") (pin "1") (pinfunction "1_1") (pintype "passive"))
    )
    (net (code "50") (name "/UMB_TDO") (class "Default")
      (node (ref "Z136") (pin "2") (pinfunction "2_2") (pintype "passive"))
      (node (ref "Z46") (pin "2") (pinfunction "2_2") (pintype "passive"))
    )
    (net (code "51") (name "/UMB_TMS") (class "Default")
      (node (ref "Z134") (pin "2") (pinfunction "2_2") (pintype "passive"))
      (node (ref "Z44") (pin "2") (pinfunction "2_2") (pintype "passive"))
    )
    (net (code "52") (name "/UMB_TX") (class "Default")
      (node (ref "Z104") (pin "1") (pinfunction "1_1") (pintype "passive"))
      (node (ref "Z53") (pin "2") (pinfunction "2_2") (pintype "passive"))
    )
    (net (code "53") (name "/VBATT") (class "Default")
      (node (ref "Z49") (pin "2") (pinfunction "2_2") (pintype "passive"))
      (node (ref "Z50") (pin "2") (pinfunction "2_2") (pintype "passive"))
      (node (ref "Z78") (pin "1") (pinfunction "1_1") (pintype "passive"))
      (node (ref "Z79") (pin "1") (pinfunction "1_1") (pintype "passive"))
    )
    (net (code "54") (name "/VBATT_IN") (class "Default")
      (node (ref "J1") (pin "1") (pinfunction "1_1") (pintype "passive"))
      (node (ref "R1") (pin "2") (pinfunction "2_2") (pintype "passive"))
      (node (ref "Z30") (pin "2") (pinfunction "2_2") (pintype "passive"))
      (node (ref "Z32") (pin "2") (pinfunction "2_2") (pintype "passive"))
    )
    (net (code "55") (name "/VBATT_SYS") (class "Default")
      (node (ref "J1") (pin "2") (pinfunction "2_2") (pintype "passive"))
      (node (ref "R1") (pin "1") (pinfunction "1_1") (pintype "passive"))
    )
    (net (code "56") (name "/VVAR_TX1") (class "Default")
      (node (ref "Z9") (pin "1") (pinfunction "1_1") (pintype "passive"))
    )
    (net (code "57") (name "/VVAR_TX1_IN") (class "Default")
      (node (ref "Z75") (pin "1") (pinfunction "1_1") (pintype "passive"))
    )
    (net (code "58") (name "/VVAR_TX2") (class "Default")
      (node (ref "Z8") (pin "1") (pinfunction "1_1") (pintype "passive"))
    )
    (net (code "59") (name "/VVAR_TX2_IN") (class "Default")
      (node (ref "Z77") (pin "1") (pinfunction "1_1") (pintype "passive"))
    )
    (net (code "60") (name "3V3_BUS") (class "Default")
      (node (ref "J6") (pin "1") (pinfunction "1_1") (pintype "passive"))
      (node (ref "R2") (pin "1") (pinfunction "1_1") (pintype "passive"))
      (node (ref "R3") (pin "1") (pinfunction "1_1") (pintype "passive"))
      (node (ref "R4") (pin "1") (pinfunction "1_1") (pintype "passive"))
      (node (ref "R5") (pin "1") (pinfunction "1_1") (pintype "passive"))
      (node (ref "R6") (pin "1") (pinfunction "1_1") (pintype "passive"))
      (node (ref "R7") (pin "1") (pinfunction "1_1") (pintype "passive"))
      (node (ref "Z21") (pin "2") (pinfunction "2_2") (pintype "passive"))
      (node (ref "Z25") (pin "2") (pinfunction "2_2") (pintype "passive"))
      (node (ref "Z59") (pin "2") (pinfunction "2_2") (pintype "passive"))
    )
    (net (code "61") (name "GND") (class "Default")
      (node (ref "J2") (pin "2") (pinfunction "2_2") (pintype "passive"))
      (node (ref "J3") (pin "2") (pinfunction "2_2") (pintype "passive"))
      (node (ref "J4") (pin "2") (pinfunction "2_2") (pintype "passive"))
      (node (ref "J5") (pin "2") (pinfunction "2_2") (pintype "passive"))
      (node (ref "J6") (pin "2") (pinfunction "2_2") (pintype "passive"))
      (node (ref "J7") (pin "2") (pinfunction "2_2") (pintype "passive"))
      (node (ref "R19") (pin "2") (pinfunction "2_2") (pintype "passive"))
      (node (ref "Z100") (pin "1") (pinfunction "1_1") (pintype "passive"))
      (node (ref "Z101") (pin "1") (pinfunction "1_1") (pintype "passive"))
      (node (ref "Z107") (pin "1") (pinfunction "1_1") (pintype "passive"))
      (node (ref "Z120") (pin "1") (pinfunction "1_1") (pintype "passive"))
      (node (ref "Z121") (pin "1") (pinfunction "1_1") (pintype "passive"))
      (node (ref "Z122") (pin "1") (pinfunction "1_1") (pintype "passive"))
      (node (ref "Z123") (pin "1") (pinfunction "1_1") (pintype "passive"))
      (node (ref "Z125") (pin "1") (pinfunction "1_1") (pintype "passive"))
      (node (ref "Z126") (pin "2") (pinfunction "2_2") (pintype "passive"))
      (node (ref "Z127") (pin "2") (pinfunction "2_2") (pintype "passive"))
      (node (ref "Z128") (pin "2") (pinfunction "2_2") (pintype "passive"))
      (node (ref "Z129") (pin "2") (pinfunction "2_2") (pintype "passive"))
      (node (ref "Z130") (pin "2") (pinfunction "2_2") (pintype "passive"))
      (node (ref "Z131") (pin "2") (pinfunction "2_2") (pintype "passive"))
      (node (ref "Z132") (pin "2") (pinfunction "2_2") (pintype "passive"))
      (node (ref "Z133") (pin "2") (pinfunction "2_2") (pintype "passive"))
      (node (ref "Z24") (pin "2") (pinfunction "2_2") (pintype "passive"))
      (node (ref "Z28") (pin "2") (pinfunction "2_2") (pintype "passive"))
      (node (ref "Z3") (pin "1") (pinfunction "1_1") (pintype "passive"))
      (node (ref "Z31") (pin "2") (pinfunction "2_2") (pintype "passive"))
      (node (ref "Z33") (pin "2") (pinfunction "2_2") (pintype "passive"))
      (node (ref "Z37") (pin "2") (pinfunction "2_2") (pintype "passive"))
      (node (ref "Z43") (pin "2") (pinfunction "2_2") (pintype "passive"))
      (node (ref "Z51") (pin "2") (pinfunction "2_2") (pintype "passive"))
      (node (ref "Z52") (pin "2") (pinfunction "2_2") (pintype "passive"))
      (node (ref "Z60") (pin "2") (pinfunction "2_2") (pintype "passive"))
      (node (ref "Z67") (pin "2") (pinfunction "2_2") (pintype "passive"))
      (node (ref "Z74") (pin "1") (pinfunction "1_1") (pintype "passive"))
      (node (ref "Z76") (pin "1") (pinfunction "1_1") (pintype "passive"))
      (node (ref "Z82") (pin "1") (pinfunction "1_1") (pintype "passive"))
      (node (ref "Z84") (pin "1") (pinfunction "1_1") (pintype "passive"))
      (node (ref "Z90") (pin "1") (pinfunction "1_1") (pintype "passive"))
      (node (ref "Z92") (pin "1") (pinfunction "1_1") (pintype "passive"))
      (node (ref "Z99") (pin "1") (pinfunction "1_1") (pintype "passive"))
    )
    (net (code "62") (name "Net-(CSCA-GND-PadA3)") (class "Default")
      (node (ref "CSC") (pin "A3") (pinfunction "GND_A3") (pintype "passive"))
      (node (ref "Z99") (pin "2") (pinfunction "2_2") (pintype "passive"))
    )
    (net (code "63") (name "Net-(CSCA-GND-PadA5)") (class "Default")
      (node (ref "CSC") (pin "A5") (pinfunction "GND_A5") (pintype "passive"))
      (node (ref "Z100") (pin "2") (pinfunction "2_2") (pintype "passive"))
    )
    (net (code "64") (name "Net-(CSCA-GND-PadA9)") (class "Default")
      (node (ref "CSC") (pin "A9") (pinfunction "GND_A9") (pintype "passive"))
      (node (ref "Z101") (pin "2") (pinfunction "2_2") (pintype "passive"))
    )
    (net (code "65") (name "Net-(CSCA-NC-PadA7)") (class "Default")
      (node (ref "CSC") (pin "A7") (pinfunction "NC_A7") (pintype "passive"))
      (node (ref "Z97") (pin "2") (pinfunction "2_2") (pintype "passive"))
    )
    (net (code "66") (name "Net-(CSCA-NC-PadA8)") (class "Default")
      (node (ref "CSC") (pin "A8") (pinfunction "NC_A8") (pintype "passive"))
      (node (ref "Z98") (pin "2") (pinfunction "2_2") (pintype "passive"))
    )
    (net (code "67") (name "Net-(CSCA-RESET)") (class "Default")
      (node (ref "CSC") (pin "A10") (pinfunction "RESET_A10") (pintype "passive"))
      (node (ref "Z137") (pin "1") (pinfunction "1_1") (pintype "passive"))
    )
    (net (code "68") (name "Net-(CSCA-SWCLK)") (class "Default")
      (node (ref "CSC") (pin "A4") (pinfunction "SWCLK_A4") (pintype "passive"))
      (node (ref "Z135") (pin "1") (pinfunction "1_1") (pintype "passive"))
    )
    (net (code "69") (name "Net-(CSCA-SWDIO)") (class "Default")
      (node (ref "CSC") (pin "A2") (pinfunction "SWDIO_A2") (pintype "passive"))
      (node (ref "Z134") (pin "1") (pinfunction "1_1") (pintype "passive"))
    )
    (net (code "70") (name "Net-(CSCA-SWO)") (class "Default")
      (node (ref "CSC") (pin "A6") (pinfunction "SWO_A6") (pintype "passive"))
      (node (ref "Z136") (pin "1") (pinfunction "1_1") (pintype "passive"))
    )
    (net (code "71") (name "Net-(CSCA-VCC)") (class "Default")
      (node (ref "CSC") (pin "A1") (pinfunction "VCC_A1") (pintype "passive"))
      (node (ref "Z96") (pin "2") (pinfunction "2_2") (pintype "passive"))
    )
    (net (code "72") (name "Net-(CSCB-CTS)") (class "Default")
      (node (ref "CSC") (pin "B5") (pinfunction "CTS_B5") (pintype "passive"))
      (node (ref "Z106") (pin "2") (pinfunction "2_2") (pintype "passive"))
    )
    (net (code "73") (name "Net-(CSCB-DTR)") (class "Default")
      (node (ref "CSC") (pin "B1") (pinfunction "DTR_B1") (pintype "passive"))
      (node (ref "Z102") (pin "2") (pinfunction "2_2") (pintype "passive"))
    )
    (net (code "74") (name "Net-(CSCB-GND)") (class "Default")
      (node (ref "CSC") (pin "B6") (pinfunction "GND_B6") (pintype "passive"))
      (node (ref "Z107") (pin "2") (pinfunction "2_2") (pintype "passive"))
    )
    (net (code "75") (name "Net-(CSCB-RXI)") (class "Default")
      (node (ref "CSC") (pin "B2") (pinfunction "RXI_B2") (pintype "passive"))
      (node (ref "Z103") (pin "2") (pinfunction "2_2") (pintype "passive"))
    )
    (net (code "76") (name "Net-(CSCB-TXO)") (class "Default")
      (node (ref "CSC") (pin "B3") (pinfunction "TXO_B3") (pintype "passive"))
      (node (ref "Z104") (pin "2") (pinfunction "2_2") (pintype "passive"))
    )
    (net (code "77") (name "Net-(CSCB-VCC)") (class "Default")
      (node (ref "CSC") (pin "B4") (pinfunction "VCC_B4") (pintype "passive"))
      (node (ref "Z105") (pin "2") (pinfunction "2_2") (pintype "passive"))
    )
    (net (code "78") (name "Net-(CSCC-GND-PadC2)") (class "Default")
      (node (ref "CSC") (pin "C2") (pinfunction "GND_C2") (pintype "passive"))
      (node (ref "Z126") (pin "1") (pinfunction "1_1") (pintype "passive"))
    )
    (net (code "79") (name "Net-(CSCC-GND-PadC4)") (class "Default")
      (node (ref "CSC") (pin "C4") (pinfunction "GND_C4") (pintype "passive"))
      (node (ref "Z127") (pin "1") (pinfunction "1_1") (pintype "passive"))
    )
    (net (code "80") (name "Net-(CSCC-GND-PadC6)") (class "Default")
      (node (ref "CSC") (pin "C6") (pinfunction "GND_C6") (pintype "passive"))
      (node (ref "Z128") (pin "1") (pinfunction "1_1") (pintype "passive"))
    )
    (net (code "81") (name "Net-(CSCC-GND-PadC8)") (class "Default")
      (node (ref "CSC") (pin "C8") (pinfunction "GND_C8") (pintype "passive"))
      (node (ref "Z129") (pin "1") (pinfunction "1_1") (pintype "passive"))
    )
    (net (code "82") (name "Net-(CSCC-GND-PadC10)") (class "Default")
      (node (ref "CSC") (pin "C10") (pinfunction "GND_C10") (pintype "passive"))
      (node (ref "Z130") (pin "1") (pinfunction "1_1") (pintype "passive"))
    )
    (net (code "83") (name "Net-(CSCC-GND-PadC12)") (class "Default")
      (node (ref "CSC") (pin "C12") (pinfunction "GND_C12") (pintype "passive"))
      (node (ref "Z131") (pin "1") (pinfunction "1_1") (pintype "passive"))
    )
    (net (code "84") (name "Net-(CSCC-GND-PadC14)") (class "Default")
      (node (ref "CSC") (pin "C14") (pinfunction "GND_C14") (pintype "passive"))
      (node (ref "Z132") (pin "1") (pinfunction "1_1") (pintype "passive"))
    )
    (net (code "85") (name "Net-(CSCC-GND-PadC16)") (class "Default")
      (node (ref "CSC") (pin "C16") (pinfunction "GND_C16") (pintype "passive"))
      (node (ref "Z133") (pin "1") (pinfunction "1_1") (pintype "passive"))
    )
    (net (code "86") (name "Net-(CSCC-G_RX1)") (class "Default")
      (node (ref "CSC") (pin "C13") (pinfunction "G_RX1_C13") (pintype "passive"))
      (node (ref "Z114") (pin "2") (pinfunction "2_2") (pintype "passive"))
    )
    (net (code "87") (name "Net-(CSCC-G_RX2)") (class "Default")
      (node (ref "CSC") (pin "C15") (pinfunction "G_RX2_C15") (pintype "passive"))
      (node (ref "Z115") (pin "2") (pinfunction "2_2") (pintype "passive"))
    )
    (net (code "88") (name "Net-(CSCC-G_TX1)") (class "Default")
      (node (ref "CSC") (pin "C9") (pinfunction "G_TX1_C9") (pintype "passive"))
      (node (ref "Z112") (pin "2") (pinfunction "2_2") (pintype "passive"))
    )
    (net (code "89") (name "Net-(CSCC-G_TX2)") (class "Default")
      (node (ref "CSC") (pin "C11") (pinfunction "G_TX2_C11") (pintype "passive"))
      (node (ref "Z113") (pin "2") (pinfunction "2_2") (pintype "passive"))
    )
    (net (code "90") (name "Net-(CSCC-RX1)") (class "Default")
      (node (ref "CSC") (pin "C5") (pinfunction "RX1_C5") (pintype "passive"))
      (node (ref "Z110") (pin "2") (pinfunction "2_2") (pintype "passive"))
    )
    (net (code "91") (name "Net-(CSCC-RX2)") (class "Default")
      (node (ref "CSC") (pin "C7") (pinfunction "RX2_C7") (pintype "passive"))
      (node (ref "Z111") (pin "2") (pinfunction "2_2") (pintype "passive"))
    )
    (net (code "92") (name "Net-(CSCC-TX1)") (class "Default")
      (node (ref "CSC") (pin "C1") (pinfunction "TX1_C1") (pintype "passive"))
      (node (ref "Z108") (pin "2") (pinfunction "2_2") (pintype "passive"))
    )
    (net (code "93") (name "Net-(CSCC-TX2)") (class "Default")
      (node (ref "CSC") (pin "C3") (pinfunction "TX2_C3") (pintype "passive"))
      (node (ref "Z109") (pin "2") (pinfunction "2_2") (pintype "passive"))
    )
    (net (code "94") (name "Net-(CSCD-3V3-PadD1)") (class "Default")
      (node (ref "CSC") (pin "D1") (pinfunction "3V3_D1") (pintype "passive"))
      (node (ref "Z116") (pin "2") (pinfunction "2_2") (pintype "passive"))
    )
    (net (code "95") (name "Net-(CSCD-3V3-PadD2)") (class "Default")
      (node (ref "CSC") (pin "D2") (pinfunction "3V3_D2") (pintype "passive"))
      (node (ref "Z117") (pin "2") (pinfunction "2_2") (pintype "passive"))
    )
    (net (code "96") (name "Net-(CSCD-3V3-PadD9)") (class "Default")
      (node (ref "CSC") (pin "D9") (pinfunction "3V3_D9") (pintype "passive"))
      (node (ref "Z118") (pin "2") (pinfunction "2_2") (pintype "passive"))
    )
    (net (code "97") (name "Net-(CSCD-3V3-PadD17)") (class "Default")
      (node (ref "CSC") (pin "D17") (pinfunction "3V3_D17") (pintype "passive"))
      (node (ref "Z119") (pin "2") (pinfunction "2_2") (pintype "passive"))
    )
    (net (code "98") (name "Net-(CSCD-EXT0)") (class "Default")
      (node (ref "CSC") (pin "D4") (pinfunction "EXT0_D4") (pintype "passive"))
      (node (ref "Z144") (pin "1") (pinfunction "1_1") (pintype "passive"))
    )
    (net (code "99") (name "Net-(CSCD-EXT1)") (class "Default")
      (node (ref "CSC") (pin "D6") (pinfunction "EXT1_D6") (pintype "passive"))
      (node (ref "Z145") (pin "1") (pinfunction "1_1") (pintype "passive"))
    )
    (net (code "100") (name "Net-(CSCD-EXT2)") (class "Default")
      (node (ref "CSC") (pin "D8") (pinfunction "EXT2_D8") (pintype "passive"))
      (node (ref "Z146") (pin "1") (pinfunction "1_1") (pintype "passive"))
    )
    (net (code "101") (name "Net-(CSCD-EXT3)") (class "Default")
      (node (ref "CSC") (pin "D10") (pinfunction "EXT3_D10") (pintype "passive"))
      (node (ref "Z147") (pin "1") (pinfunction "1_1") (pintype "passive"))
    )
    (net (code "102") (name "Net-(CSCD-EXT4)") (class "Default")
      (node (ref "CSC") (pin "D12") (pinfunction "EXT4_D12") (pintype "passive"))
      (node (ref "Z148") (pin "1") (pinfunction "1_1") (pintype "passive"))
    )
    (net (code "103") (name "Net-(CSCD-EXT5)") (class "Default")
      (node (ref "CSC") (pin "D14") (pinfunction "EXT5_D14") (pintype "passive"))
      (node (ref "Z149") (pin "1") (pinfunction "1_1") (pintype "passive"))
    )
    (net (code "104") (name "Net-(CSCD-EXT6)") (class "Default")
      (node (ref "CSC") (pin "D16") (pinfunction "EXT6_D16") (pintype "passive"))
      (node (ref "Z150") (pin "1") (pinfunction "1_1") (pintype "passive"))
    )
    (net (code "105") (name "Net-(CSCD-EXT7)") (class "Default")
      (node (ref "CSC") (pin "D18") (pinfunction "EXT7_D18") (pintype "passive"))
      (node (ref "Z151") (pin "1") (pinfunction "1_1") (pintype "passive"))
    )
    (net (code "106") (name "Net-(CSCD-EXT8)") (class "Default")
      (node (ref "CSC") (pin "D20") (pinfunction "EXT8_D20") (pintype "passive"))
      (node (ref "Z152") (pin "1") (pinfunction "1_1") (pintype "passive"))
    )
    (net (code "107") (name "Net-(CSCD-EXT9)") (class "Default")
      (node (ref "CSC") (pin "D22") (pinfunction "EXT9_D22") (pintype "passive"))
      (node (ref "Z153") (pin "1") (pinfunction "1_1") (pintype "passive"))
    )
    (net (code "108") (name "Net-(CSCD-GND-PadD7)") (class "Default")
      (node (ref "CSC") (pin "D7") (pinfunction "GND_D7") (pintype "passive"))
      (node (ref "Z120") (pin "2") (pinfunction "2_2") (pintype "passive"))
    )
    (net (code "109") (name "Net-(CSCD-GND-PadD15)") (class "Default")
      (node (ref "CSC") (pin "D15") (pinfunction "GND_D15") (pintype "passive"))
      (node (ref "Z121") (pin "2") (pinfunction "2_2") (pintype "passive"))
    )
    (net (code "110") (name "Net-(CSCD-GND-PadD23)") (class "Default")
      (node (ref "CSC") (pin "D23") (pinfunction "GND_D23") (pintype "passive"))
      (node (ref "Z122") (pin "2") (pinfunction "2_2") (pintype "passive"))
    )
    (net (code "111") (name "Net-(CSCD-GND-PadD24)") (class "Default")
      (node (ref "CSC") (pin "D24") (pinfunction "GND_D24") (pintype "passive"))
      (node (ref "Z123") (pin "2") (pinfunction "2_2") (pintype "passive"))
    )
    (net (code "112") (name "Net-(CSCD-I2C0_SCL)") (class "Default")
      (node (ref "CSC") (pin "D19") (pinfunction "I2C0_SCL_D19") (pintype "passive"))
      (node (ref "Z138") (pin "1") (pinfunction "1_1") (pintype "passive"))
    )
    (net (code "113") (name "Net-(CSCD-I2C0_SDA)") (class "Default")
      (node (ref "CSC") (pin "D21") (pinfunction "I2C0_SDA_D21") (pintype "passive"))
      (node (ref "Z139") (pin "1") (pinfunction "1_1") (pintype "passive"))
    )
    (net (code "114") (name "Net-(CSCD-I2C1_SCL)") (class "Default")
      (node (ref "CSC") (pin "D11") (pinfunction "I2C1_SCL_D11") (pintype "passive"))
      (node (ref "Z140") (pin "1") (pinfunction "1_1") (pintype "passive"))
    )
    (net (code "115") (name "Net-(CSCD-I2C1_SDA)") (class "Default")
      (node (ref "CSC") (pin "D13") (pinfunction "I2C1_SDA_D13") (pintype "passive"))
      (node (ref "Z141") (pin "1") (pinfunction "1_1") (pintype "passive"))
    )
    (net (code "116") (name "Net-(CSCD-I2C2_SCL)") (class "Default")
      (node (ref "CSC") (pin "D3") (pinfunction "I2C2_SCL_D3") (pintype "passive"))
      (node (ref "Z142") (pin "1") (pinfunction "1_1") (pintype "passive"))
    )
    (net (code "117") (name "Net-(CSCD-I2C2_SDA)") (class "Default")
      (node (ref "CSC") (pin "D5") (pinfunction "I2C2_SDA_D5") (pintype "passive"))
      (node (ref "Z143") (pin "1") (pinfunction "1_1") (pintype "passive"))
    )
    (net (code "118") (name "Net-(CSCF-EINT0)") (class "Default")
      (node (ref "CSC") (pin "F1") (pinfunction "EINT0_F1") (pintype "passive"))
      (node (ref "Z124") (pin "2") (pinfunction "2_2") (pintype "passive"))
    )
    (net (code "119") (name "Net-(CSCF-GND)") (class "Default")
      (node (ref "CSC") (pin "F2") (pinfunction "GND_F2") (pintype "passive"))
      (node (ref "Z125") (pin "2") (pinfunction "2_2") (pintype "passive"))
    )
    (net (code "120") (name "Net-(J8-Pad1)") (class "Default")
      (node (ref "J8") (pin "1") (pinfunction "1_1") (pintype "passive"))
      (node (ref "Z72") (pin "2") (pinfunction "2_2") (pintype "passive"))
    )
    (net (code "121") (name "Net-(J8-Pad2)") (class "Default")
      (node (ref "J8") (pin "2") (pinfunction "2_2") (pintype "passive"))
      (node (ref "Z73") (pin "2") (pinfunction "2_2") (pintype "passive"))
    )
    (net (code "122") (name "Net-(J8-Pad3)") (class "Default")
      (node (ref "J8") (pin "3") (pinfunction "3_3") (pintype "passive"))
      (node (ref "Z74") (pin "2") (pinfunction "2_2") (pintype "passive"))
    )
    (net (code "123") (name "Net-(J8-Pad4)") (class "Default")
      (node (ref "J8") (pin "4") (pinfunction "4_4") (pintype "passive"))
      (node (ref "Z75") (pin "2") (pinfunction "2_2") (pintype "passive"))
    )
    (net (code "124") (name "Net-(J8-Pad5)") (class "Default")
      (node (ref "J8") (pin "5") (pinfunction "5_5") (pintype "passive"))
      (node (ref "Z76") (pin "2") (pinfunction "2_2") (pintype "passive"))
    )
    (net (code "125") (name "Net-(J8-Pad6)") (class "Default")
      (node (ref "J8") (pin "6") (pinfunction "6_6") (pintype "passive"))
      (node (ref "Z77") (pin "2") (pinfunction "2_2") (pintype "passive"))
    )
    (net (code "126") (name "Net-(J8-Pad7)") (class "Default")
      (node (ref "J8") (pin "7") (pinfunction "7_7") (pintype "passive"))
      (node (ref "Z78") (pin "2") (pinfunction "2_2") (pintype "passive"))
    )
    (net (code "127") (name "Net-(J8-Pad8)") (class "Default")
      (node (ref "J8") (pin "8") (pinfunction "8_8") (pintype "passive"))
      (node (ref "Z79") (pin "2") (pinfunction "2_2") (pintype "passive"))
    )
    (net (code "128") (name "Net-(J9-Pad1)") (class "Default")
      (node (ref "J9") (pin "1") (pinfunction "1_1") (pintype "passive"))
      (node (ref "Z80") (pin "2") (pinfunction "2_2") (pintype "passive"))
    )
    (net (code "129") (name "Net-(J9-Pad2)") (class "Default")
      (node (ref "J9") (pin "2") (pinfunction "2_2") (pintype "passive"))
      (node (ref "Z81") (pin "2") (pinfunction "2_2") (pintype "passive"))
    )
    (net (code "130") (name "Net-(J9-Pad3)") (class "Default")
      (node (ref "J9") (pin "3") (pinfunction "3_3") (pintype "passive"))
      (node (ref "Z82") (pin "2") (pinfunction "2_2") (pintype "passive"))
    )
    (net (code "131") (name "Net-(J9-Pad4)") (class "Default")
      (node (ref "J9") (pin "4") (pinfunction "4_4") (pintype "passive"))
      (node (ref "Z83") (pin "2") (pinfunction "2_2") (pintype "passive"))
    )
    (net (code "132") (name "Net-(J9-Pad5)") (class "Default")
      (node (ref "J9") (pin "5") (pinfunction "5_5") (pintype "passive"))
      (node (ref "Z84") (pin "2") (pinfunction "2_2") (pintype "passive"))
    )
    (net (code "133") (name "Net-(J9-Pad6)") (class "Default")
      (node (ref "J9") (pin "6") (pinfunction "6_6") (pintype "passive"))
      (node (ref "Z85") (pin "2") (pinfunction "2_2") (pintype "passive"))
    )
    (net (code "134") (name "Net-(J9-Pad7)") (class "Default")
      (node (ref "J9") (pin "7") (pinfunction "7_7") (pintype "passive"))
      (node (ref "Z86") (pin "2") (pinfunction "2_2") (pintype "passive"))
    )
    (net (code "135") (name "Net-(J9-Pad8)") (class "Default")
      (node (ref "J9") (pin "8") (pinfunction "8_8") (pintype "passive"))
      (node (ref "Z87") (pin "2") (pinfunction "2_2") (pintype "passive"))
    )
    (net (code "136") (name "Net-(J10-Pad1)") (class "Default")
      (node (ref "J10") (pin "1") (pinfunction "1_1") (pintype "passive"))
      (node (ref "Z88") (pin "2") (pinfunction "2_2") (pintype "passive"))
    )
    (net (code "137") (name "Net-(J10-Pad2)") (class "Default")
      (node (ref "J10") (pin "2") (pinfunction "2_2") (pintype "passive"))
      (node (ref "Z89") (pin "2") (pinfunction "2_2") (pintype "passive"))
    )
    (net (code "138") (name "Net-(J10-Pad3)") (class "Default")
      (node (ref "J10") (pin "3") (pinfunction "3_3") (pintype "passive"))
      (node (ref "Z90") (pin "2") (pinfunction "2_2") (pintype "passive"))
    )
    (net (code "139") (name "Net-(J10-Pad4)") (class "Default")
      (node (ref "J10") (pin "4") (pinfunction "4_4") (pintype "passive"))
      (node (ref "Z91") (pin "2") (pinfunction "2_2") (pintype "passive"))
    )
    (net (code "140") (name "Net-(J10-Pad5)") (class "Default")
      (node (ref "J10") (pin "5") (pinfunction "5_5") (pintype "passive"))
      (node (ref "Z92") (pin "2") (pinfunction "2_2") (pintype "passive"))
    )
    (net (code "141") (name "Net-(J10-Pad6)") (class "Default")
      (node (ref "J10") (pin "6") (pinfunction "6_6") (pintype "passive"))
      (node (ref "Z93") (pin "2") (pinfunction "2_2") (pintype "passive"))
    )
    (net (code "142") (name "Net-(J10-Pad7)") (class "Default")
      (node (ref "J10") (pin "7") (pinfunction "7_7") (pintype "passive"))
      (node (ref "Z94") (pin "2") (pinfunction "2_2") (pintype "passive"))
    )
    (net (code "143") (name "Net-(J10-Pad8)") (class "Default")
      (node (ref "J10") (pin "8") (pinfunction "8_8") (pintype "passive"))
      (node (ref "Z95") (pin "2") (pinfunction "2_2") (pintype "passive"))
    )
    (net (code "144") (name "Net-(TR1-Pad1)") (class "Default")
      (node (ref "TR1") (pin "1") (pinfunction "1_1") (pintype "passive"))
      (node (ref "Z29") (pin "1") (pinfunction "1_1") (pintype "passive"))
    )
    (net (code "145") (name "Net-(TR1-Pad2)") (class "Default")
      (node (ref "TR1") (pin "2") (pinfunction "2_2") (pintype "passive"))
      (node (ref "Z27") (pin "1") (pinfunction "1_1") (pintype "passive"))
    )
    (net (code "146") (name "Net-(TR1-Pad3)") (class "Default")
      (node (ref "TR1") (pin "3") (pinfunction "3_3") (pintype "passive"))
      (node (ref "Z25") (pin "1") (pinfunction "1_1") (pintype "passive"))
    )
    (net (code "147") (name "Net-(TR1-Pad4)") (class "Default")
      (node (ref "TR1") (pin "4") (pinfunction "4_4") (pintype "passive"))
      (node (ref "Z23") (pin "1") (pinfunction "1_1") (pintype "passive"))
    )
    (net (code "148") (name "Net-(TR1-Pad5)") (class "Default")
      (node (ref "TR1") (pin "5") (pinfunction "5_5") (pintype "passive"))
      (node (ref "Z21") (pin "1") (pinfunction "1_1") (pintype "passive"))
    )
    (net (code "149") (name "Net-(TR1-Pad6)") (class "Default")
      (node (ref "TR1") (pin "6") (pinfunction "6_6") (pintype "passive"))
      (node (ref "Z28") (pin "1") (pinfunction "1_1") (pintype "passive"))
    )
    (net (code "150") (name "Net-(TR1-Pad7)") (class "Default")
      (node (ref "TR1") (pin "7") (pinfunction "7_7") (pintype "passive"))
      (node (ref "Z26") (pin "1") (pinfunction "1_1") (pintype "passive"))
    )
    (net (code "151") (name "Net-(TR1-Pad8)") (class "Default")
      (node (ref "TR1") (pin "8") (pinfunction "8_8") (pintype "passive"))
      (node (ref "Z24") (pin "1") (pinfunction "1_1") (pintype "passive"))
    )
    (net (code "152") (name "Net-(TR1-Pad9)") (class "Default")
      (node (ref "TR1") (pin "9") (pinfunction "9_9") (pintype "passive"))
      (node (ref "Z22") (pin "1") (pinfunction "1_1") (pintype "passive"))
    )
    (net (code "153") (name "Net-(TR2-Pad1)") (class "Default")
      (node (ref "TR2") (pin "1") (pinfunction "1_1") (pintype "passive"))
      (node (ref "Z70") (pin "1") (pinfunction "1_1") (pintype "passive"))
    )
    (net (code "154") (name "Net-(TR2-Pad2)") (class "Default")
      (node (ref "TR2") (pin "2") (pinfunction "2_2") (pintype "passive"))
      (node (ref "Z68") (pin "1") (pinfunction "1_1") (pintype "passive"))
    )
    (net (code "155") (name "Net-(TR2-Pad3)") (class "Default")
      (node (ref "TR2") (pin "3") (pinfunction "3_3") (pintype "passive"))
      (node (ref "Z66") (pin "1") (pinfunction "1_1") (pintype "passive"))
    )
    (net (code "156") (name "Net-(TR2-Pad4)") (class "Default")
      (node (ref "TR2") (pin "4") (pinfunction "4_4") (pintype "passive"))
      (node (ref "Z64") (pin "1") (pinfunction "1_1") (pintype "passive"))
    )
    (net (code "157") (name "Net-(TR2-Pad5)") (class "Default")
      (node (ref "TR2") (pin "5") (pinfunction "5_5") (pintype "passive"))
      (node (ref "Z62") (pin "1") (pinfunction "1_1") (pintype "passive"))
    )
    (net (code "158") (name "Net-(TR2-Pad6)") (class "Default")
      (node (ref "TR2") (pin "6") (pinfunction "6_6") (pintype "passive"))
      (node (ref "Z60") (pin "1") (pinfunction "1_1") (pintype "passive"))
    )
    (net (code "159") (name "Net-(TR2-Pad7)") (class "Default")
      (node (ref "TR2") (pin "7") (pinfunction "7_7") (pintype "passive"))
      (node (ref "Z58") (pin "1") (pinfunction "1_1") (pintype "passive"))
    )
    (net (code "160") (name "Net-(TR2-Pad8)") (class "Default")
      (node (ref "TR2") (pin "8") (pinfunction "8_8") (pintype "passive"))
      (node (ref "Z56") (pin "1") (pinfunction "1_1") (pintype "passive"))
    )
    (net (code "161") (name "Net-(TR2-Pad9)") (class "Default")
      (node (ref "TR2") (pin "9") (pinfunction "9_9") (pintype "passive"))
      (node (ref "Z54") (pin "1") (pinfunction "1_1") (pintype "passive"))
    )
    (net (code "162") (name "Net-(TR2-Pad10)") (class "Default")
      (node (ref "TR2") (pin "10") (pinfunction "10_10") (pintype "passive"))
      (node (ref "Z52") (pin "1") (pinfunction "1_1") (pintype "passive"))
    )
    (net (code "163") (name "Net-(TR2-Pad11)") (class "Default")
      (node (ref "TR2") (pin "11") (pinfunction "11_11") (pintype "passive"))
      (node (ref "Z50") (pin "1") (pinfunction "1_1") (pintype "passive"))
    )
    (net (code "164") (name "Net-(TR2-Pad12)") (class "Default")
      (node (ref "TR2") (pin "12") (pinfunction "12_12") (pintype "passive"))
      (node (ref "Z48") (pin "1") (pinfunction "1_1") (pintype "passive"))
    )
    (net (code "165") (name "Net-(TR2-Pad13)") (class "Default")
      (node (ref "TR2") (pin "13") (pinfunction "13_13") (pintype "passive"))
      (node (ref "Z46") (pin "1") (pinfunction "1_1") (pintype "passive"))
    )
    (net (code "166") (name "Net-(TR2-Pad14)") (class "Default")
      (node (ref "TR2") (pin "14") (pinfunction "14_14") (pintype "passive"))
      (node (ref "Z44") (pin "1") (pinfunction "1_1") (pintype "passive"))
    )
    (net (code "167") (name "Net-(TR2-Pad15)") (class "Default")
      (node (ref "TR2") (pin "15") (pinfunction "15_15") (pintype "passive"))
      (node (ref "Z42") (pin "1") (pinfunction "1_1") (pintype "passive"))
    )
    (net (code "168") (name "Net-(TR2-Pad16)") (class "Default")
      (node (ref "TR2") (pin "16") (pinfunction "16_16") (pintype "passive"))
      (node (ref "Z40") (pin "1") (pinfunction "1_1") (pintype "passive"))
    )
    (net (code "169") (name "Net-(TR2-Pad17)") (class "Default")
      (node (ref "TR2") (pin "17") (pinfunction "17_17") (pintype "passive"))
      (node (ref "Z38") (pin "1") (pinfunction "1_1") (pintype "passive"))
    )
    (net (code "170") (name "Net-(TR2-Pad18)") (class "Default")
      (node (ref "TR2") (pin "18") (pinfunction "18_18") (pintype "passive"))
      (node (ref "Z36") (pin "1") (pinfunction "1_1") (pintype "passive"))
    )
    (net (code "171") (name "Net-(TR2-Pad19)") (class "Default")
      (node (ref "TR2") (pin "19") (pinfunction "19_19") (pintype "passive"))
      (node (ref "Z34") (pin "1") (pinfunction "1_1") (pintype "passive"))
    )
    (net (code "172") (name "Net-(TR2-Pad20)") (class "Default")
      (node (ref "TR2") (pin "20") (pinfunction "20_20") (pintype "passive"))
      (node (ref "Z32") (pin "1") (pinfunction "1_1") (pintype "passive"))
    )
    (net (code "173") (name "Net-(TR2-Pad21)") (class "Default")
      (node (ref "TR2") (pin "21") (pinfunction "21_21") (pintype "passive"))
      (node (ref "Z30") (pin "1") (pinfunction "1_1") (pintype "passive"))
    )
    (net (code "174") (name "Net-(TR2-Pad22)") (class "Default")
      (node (ref "TR2") (pin "22") (pinfunction "22_22") (pintype "passive"))
      (node (ref "Z71") (pin "1") (pinfunction "1_1") (pintype "passive"))
    )
    (net (code "175") (name "Net-(TR2-Pad23)") (class "Default")
      (node (ref "TR2") (pin "23") (pinfunction "23_23") (pintype "passive"))
      (node (ref "Z69") (pin "1") (pinfunction "1_1") (pintype "passive"))
    )
    (net (code "176") (name "Net-(TR2-Pad24)") (class "Default")
      (node (ref "TR2") (pin "24") (pinfunction "24_24") (pintype "passive"))
      (node (ref "Z67") (pin "1") (pinfunction "1_1") (pintype "passive"))
    )
    (net (code "177") (name "Net-(TR2-Pad25)") (class "Default")
      (node (ref "TR2") (pin "25") (pinfunction "25_25") (pintype "passive"))
      (node (ref "Z65") (pin "1") (pinfunction "1_1") (pintype "passive"))
    )
    (net (code "178") (name "Net-(TR2-Pad26)") (class "Default")
      (node (ref "TR2") (pin "26") (pinfunction "26_26") (pintype "passive"))
      (node (ref "Z63") (pin "1") (pinfunction "1_1") (pintype "passive"))
    )
    (net (code "179") (name "Net-(TR2-Pad27)") (class "Default")
      (node (ref "TR2") (pin "27") (pinfunction "27_27") (pintype "passive"))
      (node (ref "Z61") (pin "1") (pinfunction "1_1") (pintype "passive"))
    )
    (net (code "180") (name "Net-(TR2-Pad28)") (class "Default")
      (node (ref "TR2") (pin "28") (pinfunction "28_28") (pintype "passive"))
      (node (ref "Z59") (pin "1") (pinfunction "1_1") (pintype "passive"))
    )
    (net (code "181") (name "Net-(TR2-Pad29)") (class "Default")
      (node (ref "TR2") (pin "29") (pinfunction "29_29") (pintype "passive"))
      (node (ref "Z57") (pin "1") (pinfunction "1_1") (pintype "passive"))
    )
    (net (code "182") (name "Net-(TR2-Pad30)") (class "Default")
      (node (ref "TR2") (pin "30") (pinfunction "30_30") (pintype "passive"))
      (node (ref "Z55") (pin "1") (pinfunction "1_1") (pintype "passive"))
    )
    (net (code "183") (name "Net-(TR2-Pad31)") (class "Default")
      (node (ref "TR2") (pin "31") (pinfunction "31_31") (pintype "passive"))
      (node (ref "Z53") (pin "1") (pinfunction "1_1") (pintype "passive"))
    )
    (net (code "184") (name "Net-(TR2-Pad32)") (class "Default")
      (node (ref "TR2") (pin "32") (pinfunction "32_32") (pintype "passive"))
      (node (ref "Z51") (pin "1") (pinfunction "1_1") (pintype "passive"))
    )
    (net (code "185") (name "Net-(TR2-Pad33)") (class "Default")
      (node (ref "TR2") (pin "33") (pinfunction "33_33") (pintype "passive"))
      (node (ref "Z49") (pin "1") (pinfunction "1_1") (pintype "passive"))
    )
    (net (code "186") (name "Net-(TR2-Pad34)") (class "Default")
      (node (ref "TR2") (pin "34") (pinfunction "34_34") (pintype "passive"))
      (node (ref "Z47") (pin "1") (pinfunction "1_1") (pintype "passive"))
    )
    (net (code "187") (name "Net-(TR2-Pad35)") (class "Default")
      (node (ref "TR2") (pin "35") (pinfunction "35_35") (pintype "passive"))
      (node (ref "Z45") (pin "1") (pinfunction "1_1") (pintype "passive"))
    )
    (net (code "188") (name "Net-(TR2-Pad36)") (class "Default")
      (node (ref "TR2") (pin "36") (pinfunction "36_36") (pintype "passive"))
      (node (ref "Z43") (pin "1") (pinfunction "1_1") (pintype "passive"))
    )
    (net (code "189") (name "Net-(TR2-Pad37)") (class "Default")
      (node (ref "TR2") (pin "37") (pinfunction "37_37") (pintype "passive"))
      (node (ref "Z41") (pin "1") (pinfunction "1_1") (pintype "passive"))
    )
    (net (code "190") (name "Net-(TR2-Pad38)") (class "Default")
      (node (ref "TR2") (pin "38") (pinfunction "38_38") (pintype "passive"))
      (node (ref "Z39") (pin "1") (pinfunction "1_1") (pintype "passive"))
    )
    (net (code "191") (name "Net-(TR2-Pad39)") (class "Default")
      (node (ref "TR2") (pin "39") (pinfunction "39_39") (pintype "passive"))
      (node (ref "Z37") (pin "1") (pinfunction "1_1") (pintype "passive"))
    )
    (net (code "192") (name "Net-(TR2-Pad40)") (class "Default")
      (node (ref "TR2") (pin "40") (pinfunction "40_40") (pintype "passive"))
      (node (ref "Z35") (pin "1") (pinfunction "1_1") (pintype "passive"))
    )
    (net (code "193") (name "Net-(TR2-Pad41)") (class "Default")
      (node (ref "TR2") (pin "41") (pinfunction "41_41") (pintype "passive"))
      (node (ref "Z33") (pin "1") (pinfunction "1_1") (pintype "passive"))
    )
    (net (code "194") (name "Net-(TR2-Pad42)") (class "Default")
      (node (ref "TR2") (pin "42") (pinfunction "42_42") (pintype "passive"))
      (node (ref "Z31") (pin "1") (pinfunction "1_1") (pintype "passive"))
    )
    (net (code "195") (name "Net-(TR2-Pad43)") (class "Default")
      (node (ref "TR2") (pin "43") (pinfunction "43_43") (pintype "passive"))
      (node (ref "Z20") (pin "2") (pinfunction "2_2") (pintype "passive"))
    )
    (net (code "196") (name "Net-(TR2-Pad44)") (class "Default")
      (node (ref "TR2") (pin "44") (pinfunction "44_44") (pintype "passive"))
      (node (ref "Z19") (pin "2") (pinfunction "2_2") (pintype "passive"))
    )
    (net (code "197") (name "Net-(TR2-Pad45)") (class "Default")
      (node (ref "TR2") (pin "45") (pinfunction "45_45") (pintype "passive"))
      (node (ref "Z18") (pin "2") (pinfunction "2_2") (pintype "passive"))
    )
    (net (code "198") (name "Net-(TR2-Pad46)") (class "Default")
      (node (ref "TR2") (pin "46") (pinfunction "46_46") (pintype "passive"))
      (node (ref "Z17") (pin "2") (pinfunction "2_2") (pintype "passive"))
    )
    (net (code "199") (name "Net-(TR2-Pad47)") (class "Default")
      (node (ref "TR2") (pin "47") (pinfunction "47_47") (pintype "passive"))
      (node (ref "Z16") (pin "2") (pinfunction "2_2") (pintype "passive"))
    )
    (net (code "200") (name "Net-(TR2-Pad48)") (class "Default")
      (node (ref "TR2") (pin "48") (pinfunction "48_48") (pintype "passive"))
      (node (ref "Z15") (pin "2") (pinfunction "2_2") (pintype "passive"))
    )
    (net (code "201") (name "Net-(TR2-Pad49)") (class "Default")
      (node (ref "TR2") (pin "49") (pinfunction "49_49") (pintype "passive"))
      (node (ref "Z14") (pin "2") (pinfunction "2_2") (pintype "passive"))
    )
    (net (code "202") (name "Net-(TR2-Pad50)") (class "Default")
      (node (ref "TR2") (pin "50") (pinfunction "50_50") (pintype "passive"))
      (node (ref "Z13") (pin "2") (pinfunction "2_2") (pintype "passive"))
    )
    (net (code "203") (name "Net-(TR2-Pad51)") (class "Default")
      (node (ref "TR2") (pin "51") (pinfunction "51_51") (pintype "passive"))
      (node (ref "Z12") (pin "2") (pinfunction "2_2") (pintype "passive"))
    )
    (net (code "204") (name "Net-(TR2-Pad52)") (class "Default")
      (node (ref "TR2") (pin "52") (pinfunction "52_52") (pintype "passive"))
      (node (ref "Z11") (pin "2") (pinfunction "2_2") (pintype "passive"))
    )
    (net (code "205") (name "Net-(TR2-Pad53)") (class "Default")
      (node (ref "TR2") (pin "53") (pinfunction "53_53") (pintype "passive"))
      (node (ref "Z10") (pin "2") (pinfunction "2_2") (pintype "passive"))
    )
    (net (code "206") (name "Net-(TR2-Pad54)") (class "Default")
      (node (ref "TR2") (pin "54") (pinfunction "54_54") (pintype "passive"))
      (node (ref "Z9") (pin "2") (pinfunction "2_2") (pintype "passive"))
    )
    (net (code "207") (name "Net-(TR2-Pad55)") (class "Default")
      (node (ref "TR2") (pin "55") (pinfunction "55_55") (pintype "passive"))
      (node (ref "Z8") (pin "2") (pinfunction "2_2") (pintype "passive"))
    )
    (net (code "208") (name "Net-(TR2-Pad56)") (class "Default")
      (node (ref "TR2") (pin "56") (pinfunction "56_56") (pintype "passive"))
      (node (ref "Z7") (pin "2") (pinfunction "2_2") (pintype "passive"))
    )
    (net (code "209") (name "Net-(TR2-Pad57)") (class "Default")
      (node (ref "TR2") (pin "57") (pinfunction "57_57") (pintype "passive"))
      (node (ref "Z6") (pin "2") (pinfunction "2_2") (pintype "passive"))
    )
    (net (code "210") (name "Net-(TR2-Pad58)") (class "Default")
      (node (ref "TR2") (pin "58") (pinfunction "58_58") (pintype "passive"))
      (node (ref "Z5") (pin "2") (pinfunction "2_2") (pintype "passive"))
    )
    (net (code "211") (name "Net-(TR2-Pad59)") (class "Default")
      (node (ref "TR2") (pin "59") (pinfunction "59_59") (pintype "passive"))
      (node (ref "Z4") (pin "2") (pinfunction "2_2") (pintype "passive"))
    )
    (net (code "212") (name "Net-(TR2-Pad60)") (class "Default")
      (node (ref "TR2") (pin "60") (pinfunction "60_60") (pintype "passive"))
      (node (ref "Z3") (pin "2") (pinfunction "2_2") (pintype "passive"))
    )
    (net (code "213") (name "Net-(TR2-Pad61)") (class "Default")
      (node (ref "TR2") (pin "61") (pinfunction "61_61") (pintype "passive"))
      (node (ref "Z2") (pin "2") (pinfunction "2_2") (pintype "passive"))
    )
    (net (code "214") (name "Net-(TR2-Pad62)") (class "Default")
      (node (ref "TR2") (pin "62") (pinfunction "62_62") (pintype "passive"))
      (node (ref "Z1") (pin "2") (pinfunction "2_2") (pintype "passive"))
    )
    (net (code "215") (name "unconnected-(CSCE-SCREW1-PadE1)") (class "Default")
      (node (ref "CSC") (pin "E1") (pinfunction "SCREW1_E1") (pintype "passive+no_connect"))
    )
    (net (code "216") (name "unconnected-(CSCE-SCREW2-PadE2)") (class "Default")
      (node (ref "CSC") (pin "E2") (pinfunction "SCREW2_E2") (pintype "passive+no_connect"))
    )
    (net (code "217") (name "unconnected-(CSCE-SCREW3-PadE3)") (class "Default")
      (node (ref "CSC") (pin "E3") (pinfunction "SCREW3_E3") (pintype "passive+no_connect"))
    )
    (net (code "218") (name "unconnected-(CSCE-SCREW4-PadE4)") (class "Default")
      (node (ref "CSC") (pin "E4") (pinfunction "SCREW4_E4") (pintype "passive+no_connect"))
    )
    (net (code "219") (name "unconnected-(TR1-MH1-Pad10)") (class "Default")
      (node (ref "TR1") (pin "10") (pinfunction "MH1_10") (pintype "passive+no_connect"))
    )
    (net (code "220") (name "unconnected-(TR1-MH2-Pad11)") (class "Default")
      (node (ref "TR1") (pin "11") (pinfunction "MH2_11") (pintype "passive+no_connect"))
    )
    (net (code "221") (name "unconnected-(TR2-MH1-Pad63)") (class "Default")
      (node (ref "TR2") (pin "63") (pinfunction "MH1_63") (pintype "passive+no_connect"))
    )
    (net (code "222") (name "unconnected-(TR2-MH2-Pad64)") (class "Default")
      (node (ref "TR2") (pin "64") (pinfunction "MH2_64") (pintype "passive+no_connect"))
    )
    (net (code "223") (name "unconnected-(Z10-Pad1)") (class "Default")
      (node (ref "Z10") (pin "1") (pinfunction "1_1") (pintype "passive+no_connect"))
    )
    (net (code "224") (name "unconnected-(Z11-Pad1)") (class "Default")
      (node (ref "Z11") (pin "1") (pinfunction "1_1") (pintype "passive+no_connect"))
    )
    (net (code "225") (name "unconnected-(Z12-Pad1)") (class "Default")
      (node (ref "Z12") (pin "1") (pinfunction "1_1") (pintype "passive+no_connect"))
    )
    (net (code "226") (name "unconnected-(Z13-Pad1)") (class "Default")
      (node (ref "Z13") (pin "1") (pinfunction "1_1") (pintype "passive+no_connect"))
    )
    (net (code "227") (name "unconnected-(Z14-Pad1)") (class "Default")
      (node (ref "Z14") (pin "1") (pinfunction "1_1") (pintype "passive+no_connect"))
    )
    (net (code "228") (name "unconnected-(Z15-Pad1)") (class "Default")
      (node (ref "Z15") (pin "1") (pinfunction "1_1") (pintype "passive+no_connect"))
    )
    (net (code "229") (name "unconnected-(Z16-Pad1)") (class "Default")
      (node (ref "Z16") (pin "1") (pinfunction "1_1") (pintype "passive+no_connect"))
    )
    (net (code "230") (name "unconnected-(Z17-Pad1)") (class "Default")
      (node (ref "Z17") (pin "1") (pinfunction "1_1") (pintype "passive+no_connect"))
    )
    (net (code "231") (name "unconnected-(Z18-Pad1)") (class "Default")
      (node (ref "Z18") (pin "1") (pinfunction "1_1") (pintype "passive+no_connect"))
    )
    (net (code "232") (name "unconnected-(Z19-Pad1)") (class "Default")
      (node (ref "Z19") (pin "1") (pinfunction "1_1") (pintype "passive+no_connect"))
    )
    (net (code "233") (name "unconnected-(Z20-Pad1)") (class "Default")
      (node (ref "Z20") (pin "1") (pinfunction "1_1") (pintype "passive+no_connect"))
    )
    (net (code "234") (name "unconnected-(Z29-Pad2)") (class "Default")
      (node (ref "Z29") (pin "2") (pinfunction "2_2") (pintype "passive"))
    )
    (net (code "235") (name "unconnected-(Z61-Pad2)") (class "Default")
      (node (ref "Z61") (pin "2") (pinfunction "2_2") (pintype "passive+no_connect"))
    )
    (net (code "236") (name "unconnected-(Z62-Pad2)") (class "Default")
      (node (ref "Z62") (pin "2") (pinfunction "2_2") (pintype "passive+no_connect"))
    )
    (net (code "237") (name "unconnected-(Z102-Pad1)") (class "Default")
      (node (ref "Z102") (pin "1") (pinfunction "1_1") (pintype "passive+no_connect"))
    )
    (net (code "238") (name "unconnected-(Z105-Pad1)") (class "Default")
      (node (ref "Z105") (pin "1") (pinfunction "1_1") (pintype "passive+no_connect"))
    )
    (net (code "239") (name "unconnected-(Z106-Pad1)") (class "Default")
      (node (ref "Z106") (pin "1") (pinfunction "1_1") (pintype "passive+no_connect"))
    )
    (net (code "240") (name "unconnected-(Z148-Pad2)") (class "Default")
      (node (ref "Z148") (pin "2") (pinfunction "2_2") (pintype "passive+no_connect"))
    )
    (net (code "241") (name "unconnected-(Z149-Pad2)") (class "Default")
      (node (ref "Z149") (pin "2") (pinfunction "2_2") (pintype "passive+no_connect"))
    )
    (net (code "242") (name "unconnected-(Z150-Pad2)") (class "Default")
      (node (ref "Z150") (pin "2") (pinfunction "2_2") (pintype "passive+no_connect"))
    )
    (net (code "243") (name "unconnected-(Z151-Pad2)") (class "Default")
      (node (ref "Z151") (pin "2") (pinfunction "2_2") (pintype "passive+no_connect"))
    )
    (net (code "244") (name "unconnected-(Z152-Pad2)") (class "Default")
      (node (ref "Z152") (pin "2") (pinfunction "2_2") (pintype "passive+no_connect"))
    )
    (net (code "245") (name "unconnected-(Z153-Pad2)") (class "Default")
      (node (ref "Z153") (pin "2") (pinfunction "2_2") (pintype "passive+no_connect"))
    )
  )
)
